# dualwbo.net
KiCad netlist of a schematic drawn in EAGLE
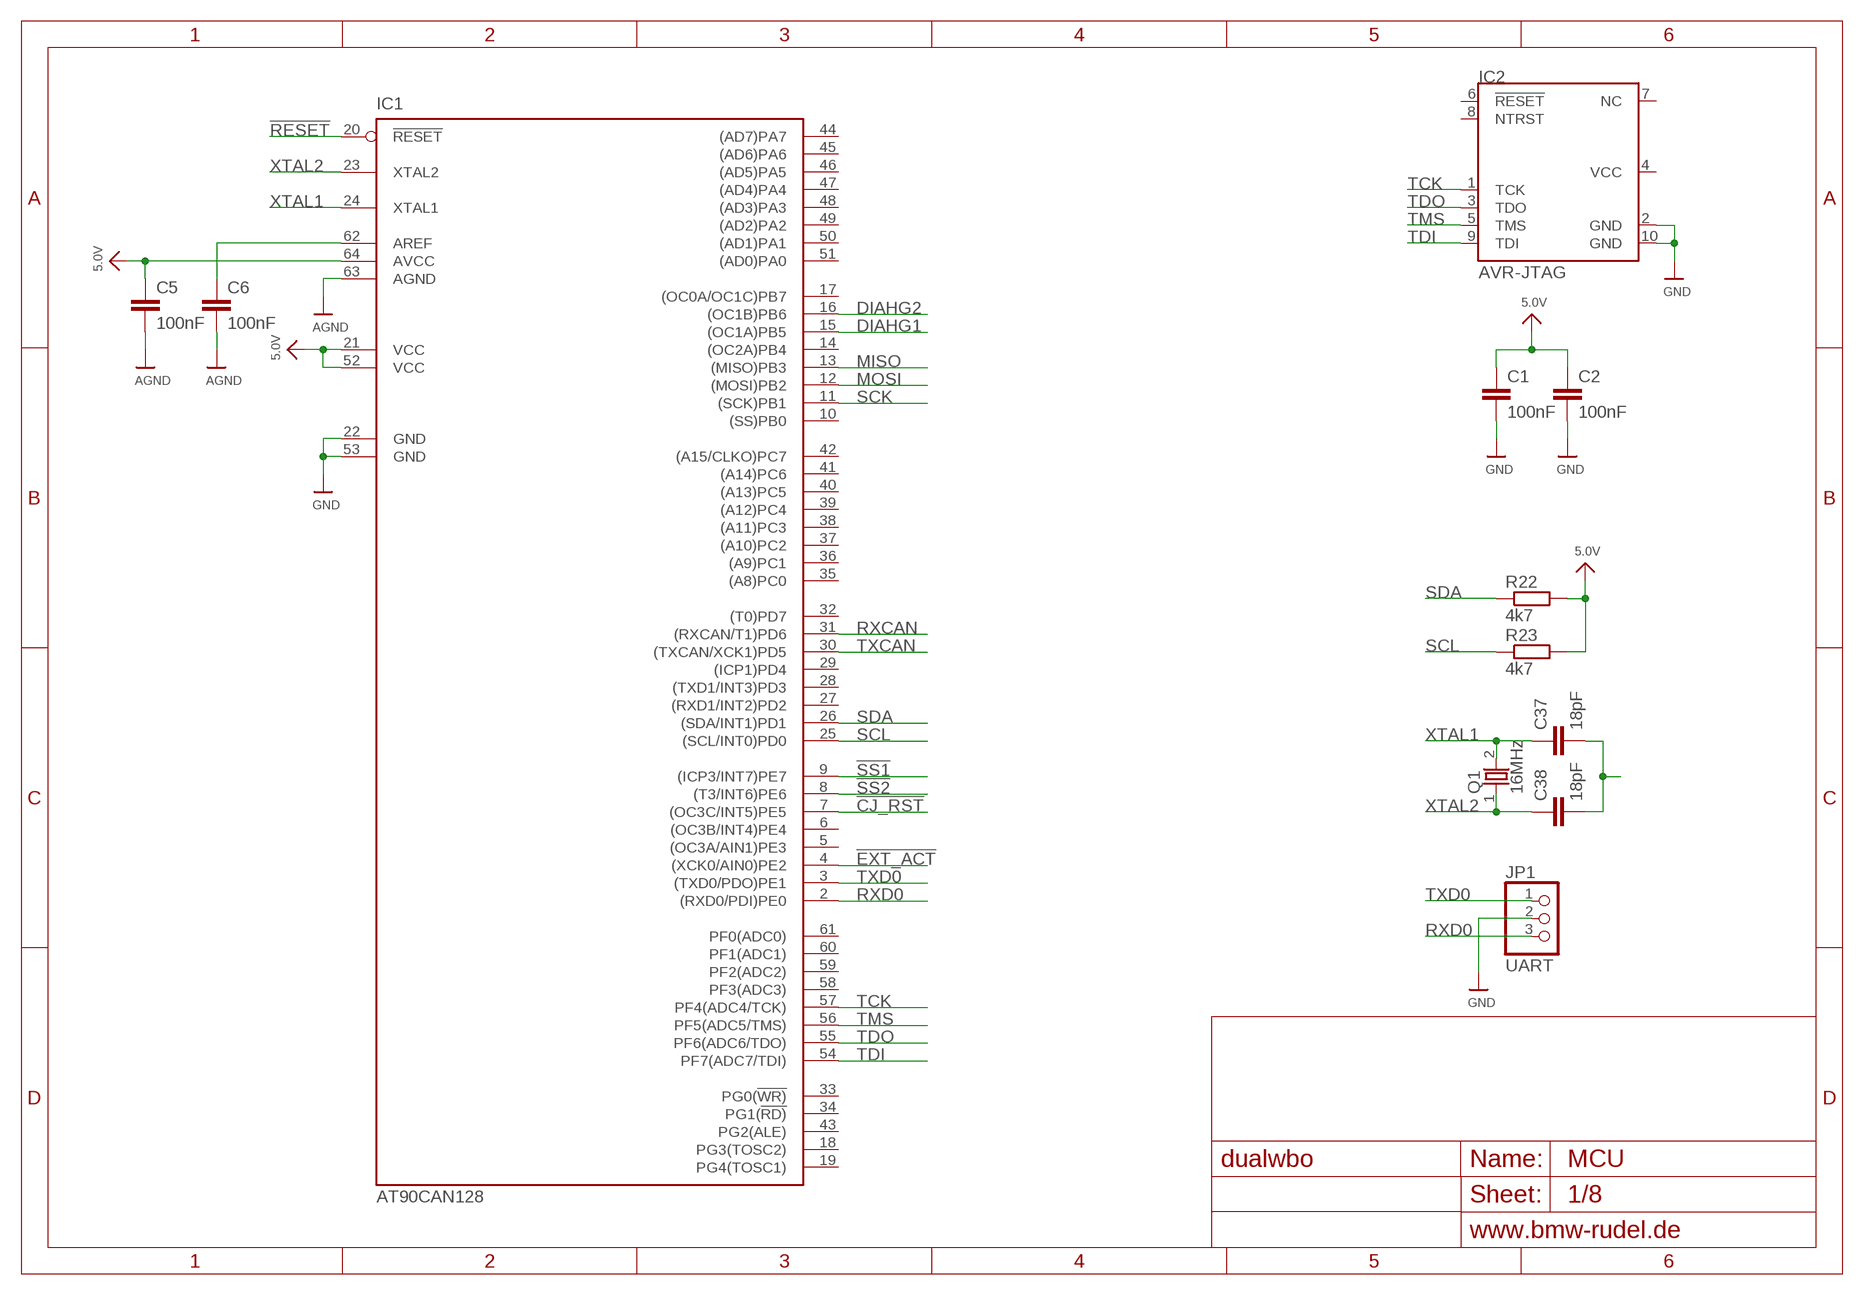
[diagram p0: schematic, sheet 1]
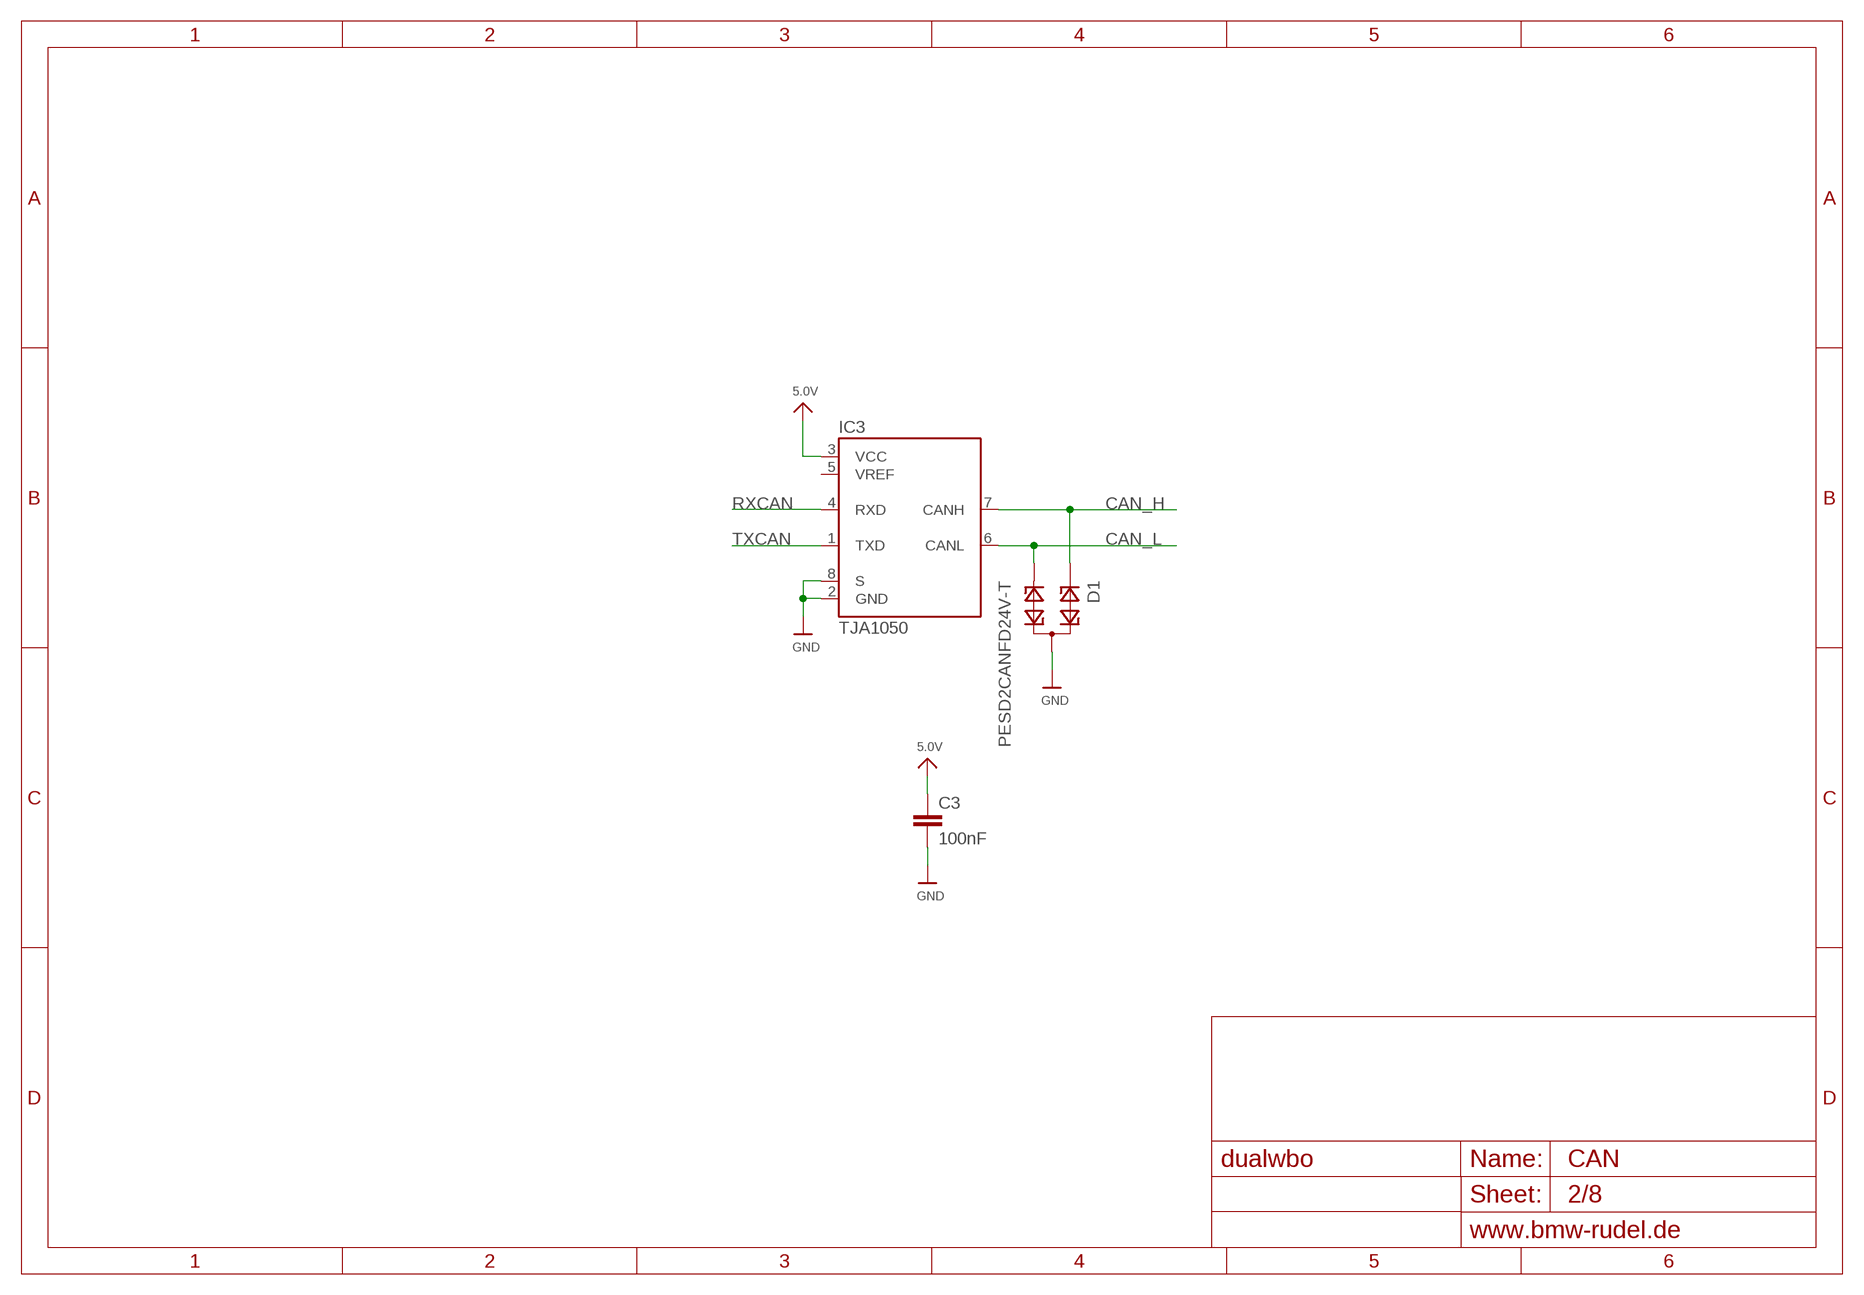
[diagram p1: schematic, sheet 2]
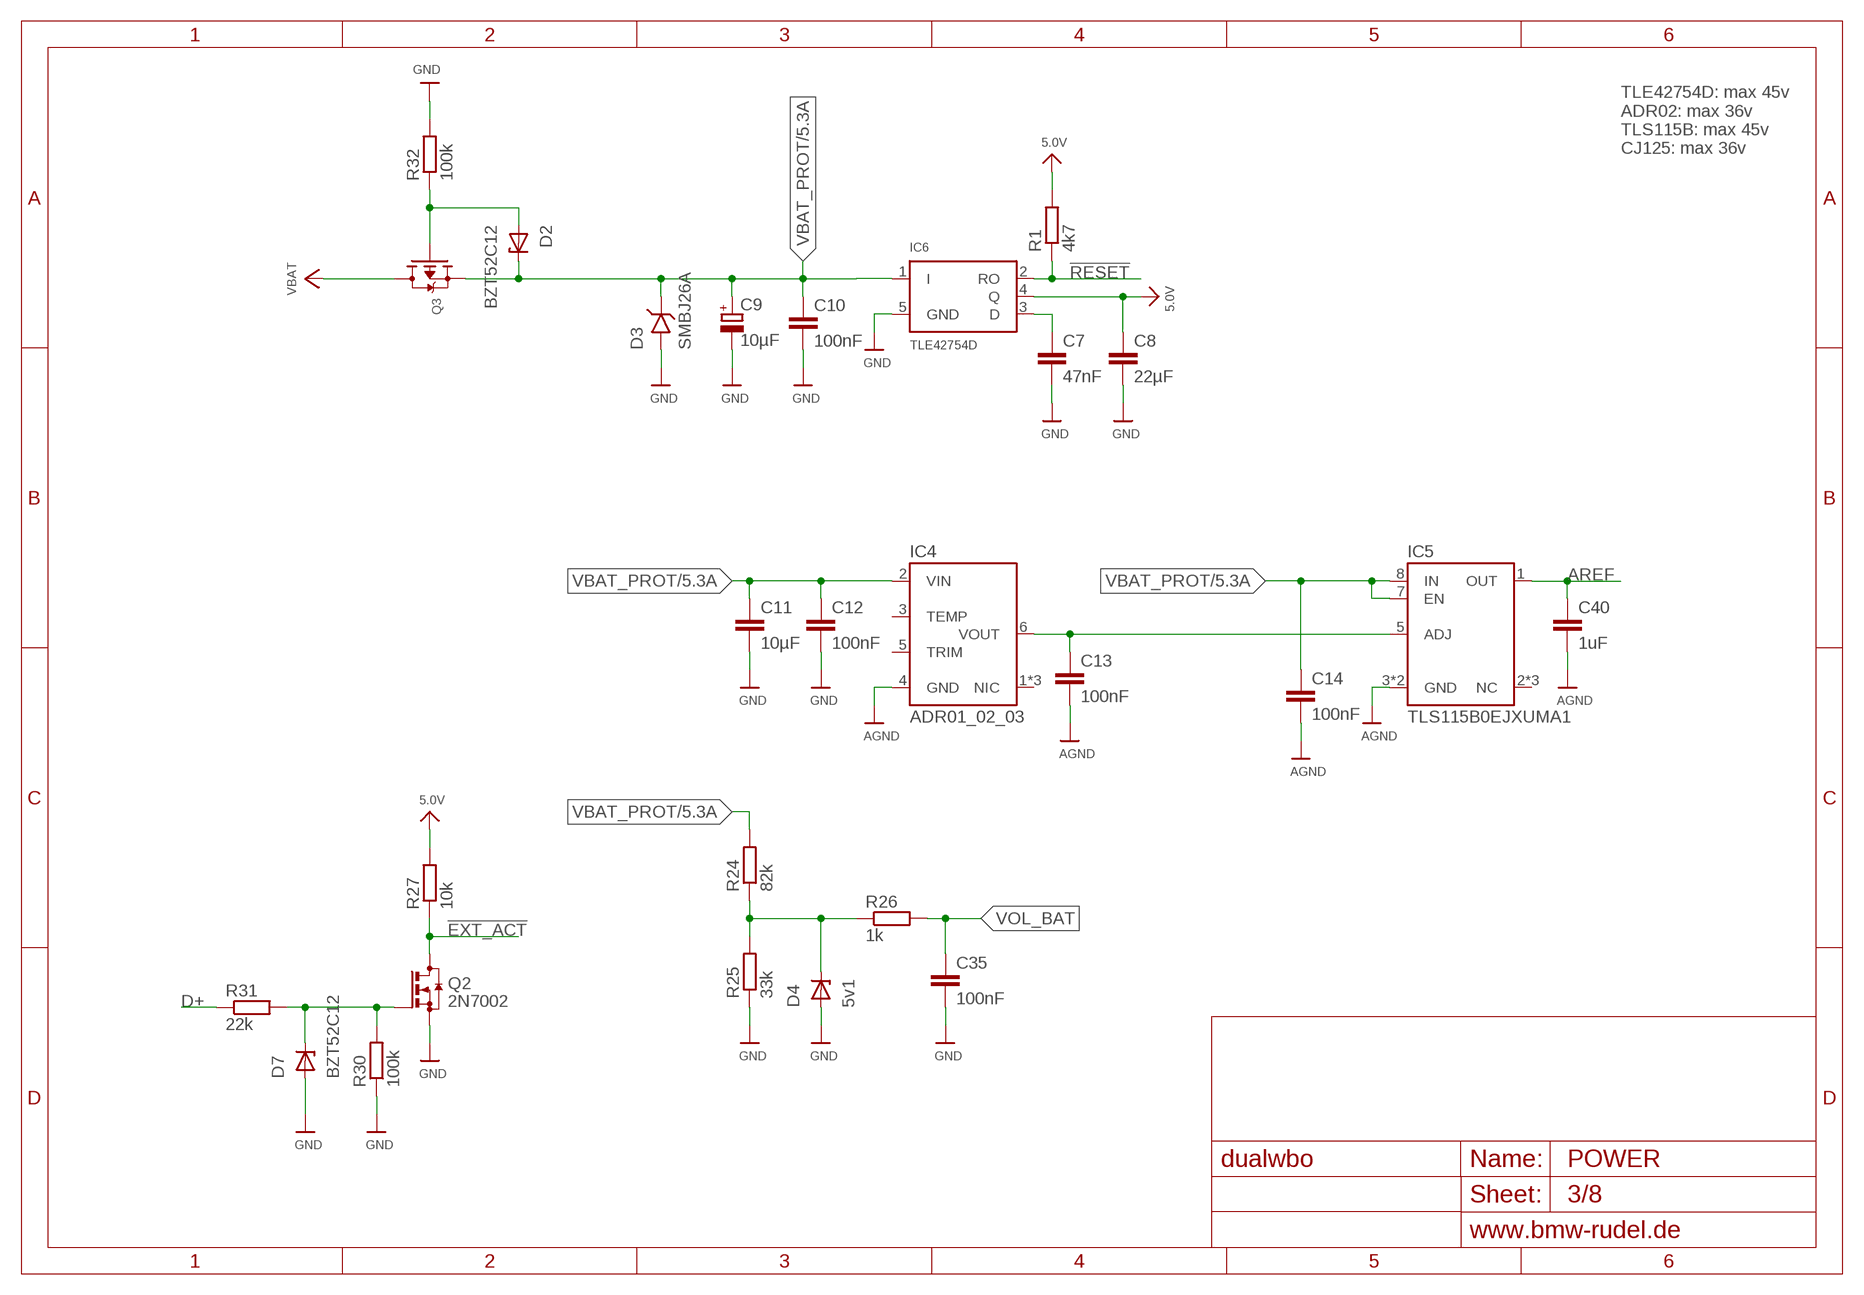
[diagram p2: schematic, sheet 3]
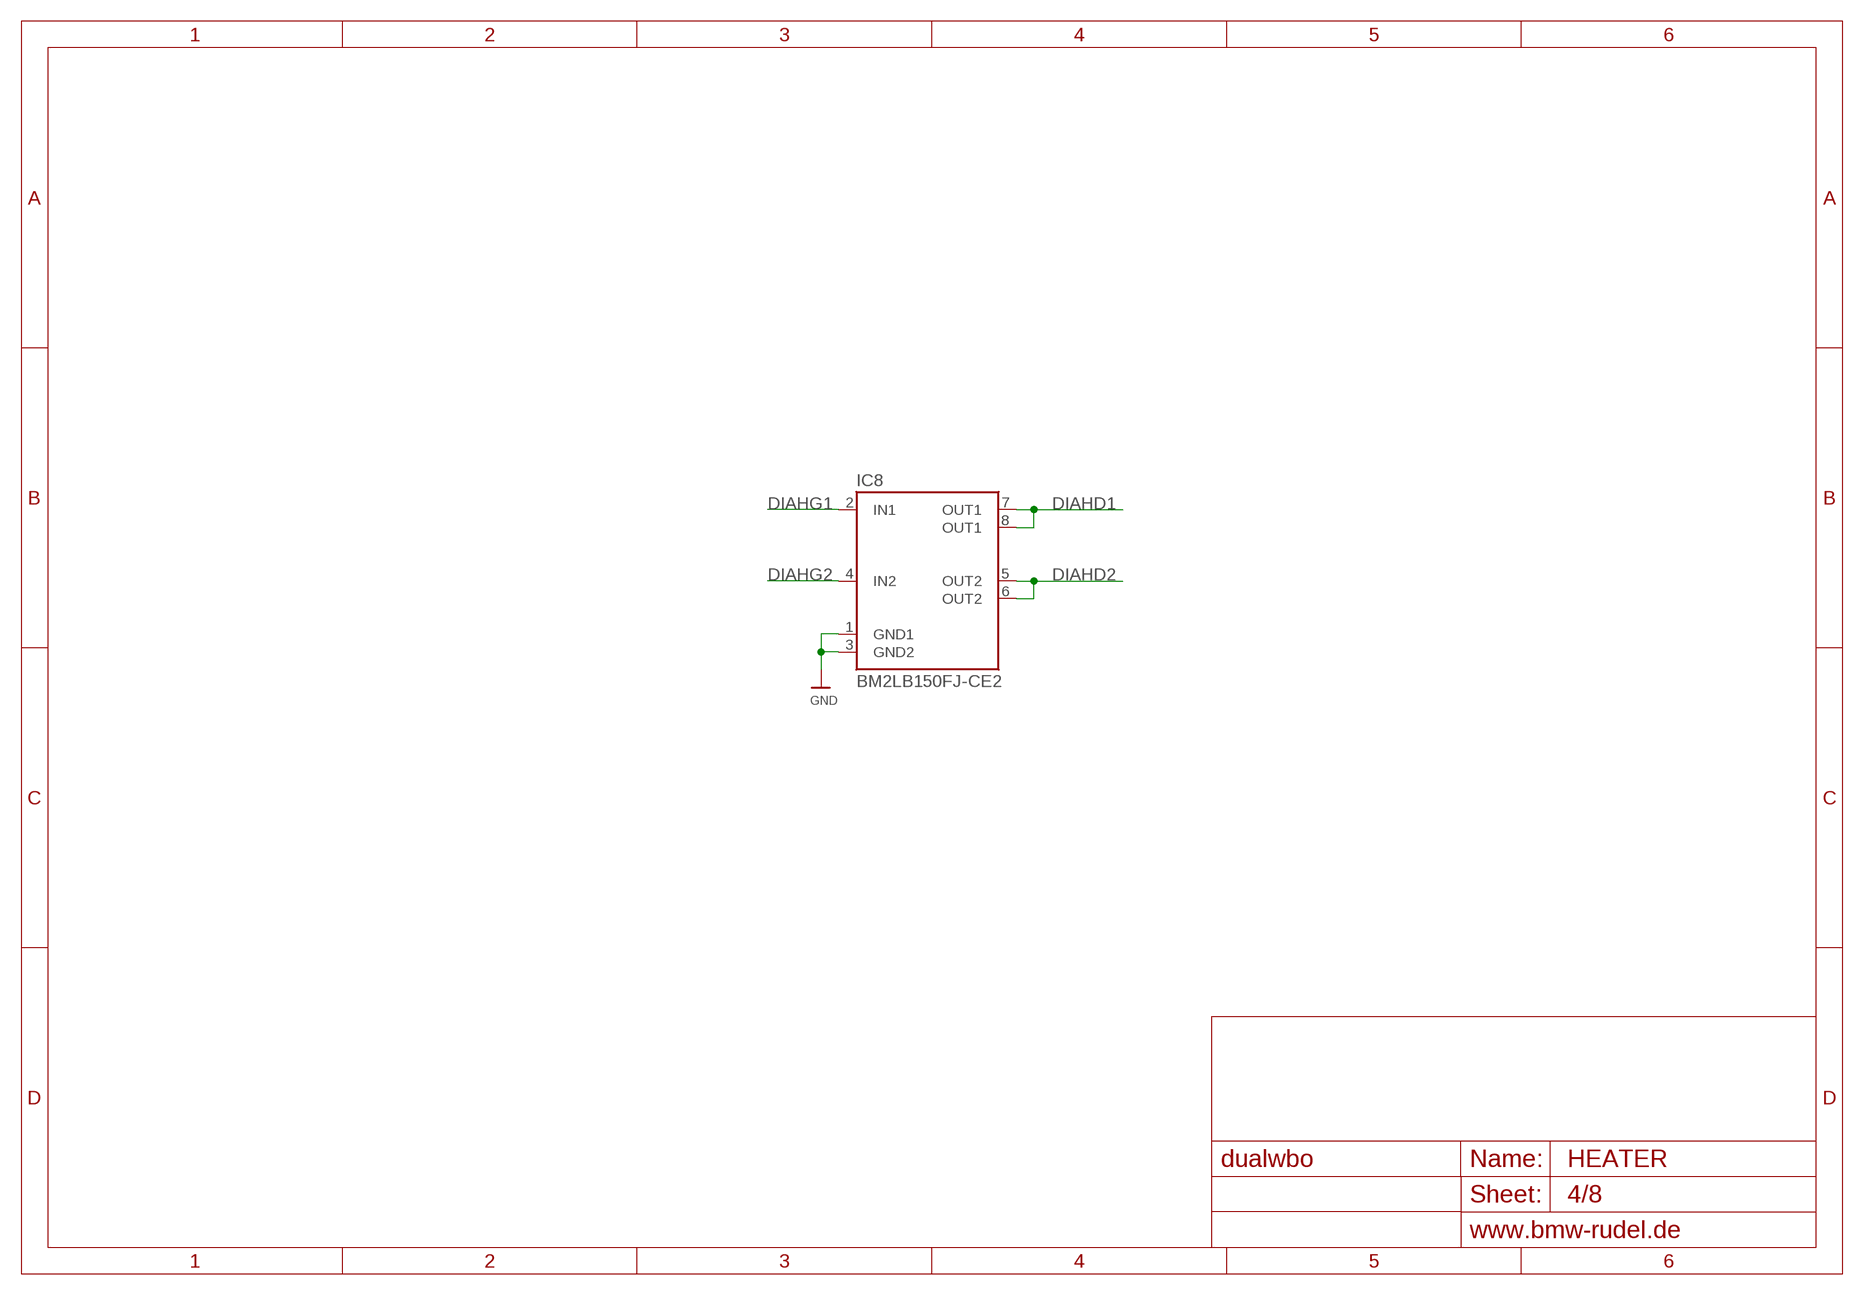
[diagram p3: schematic, sheet 4]
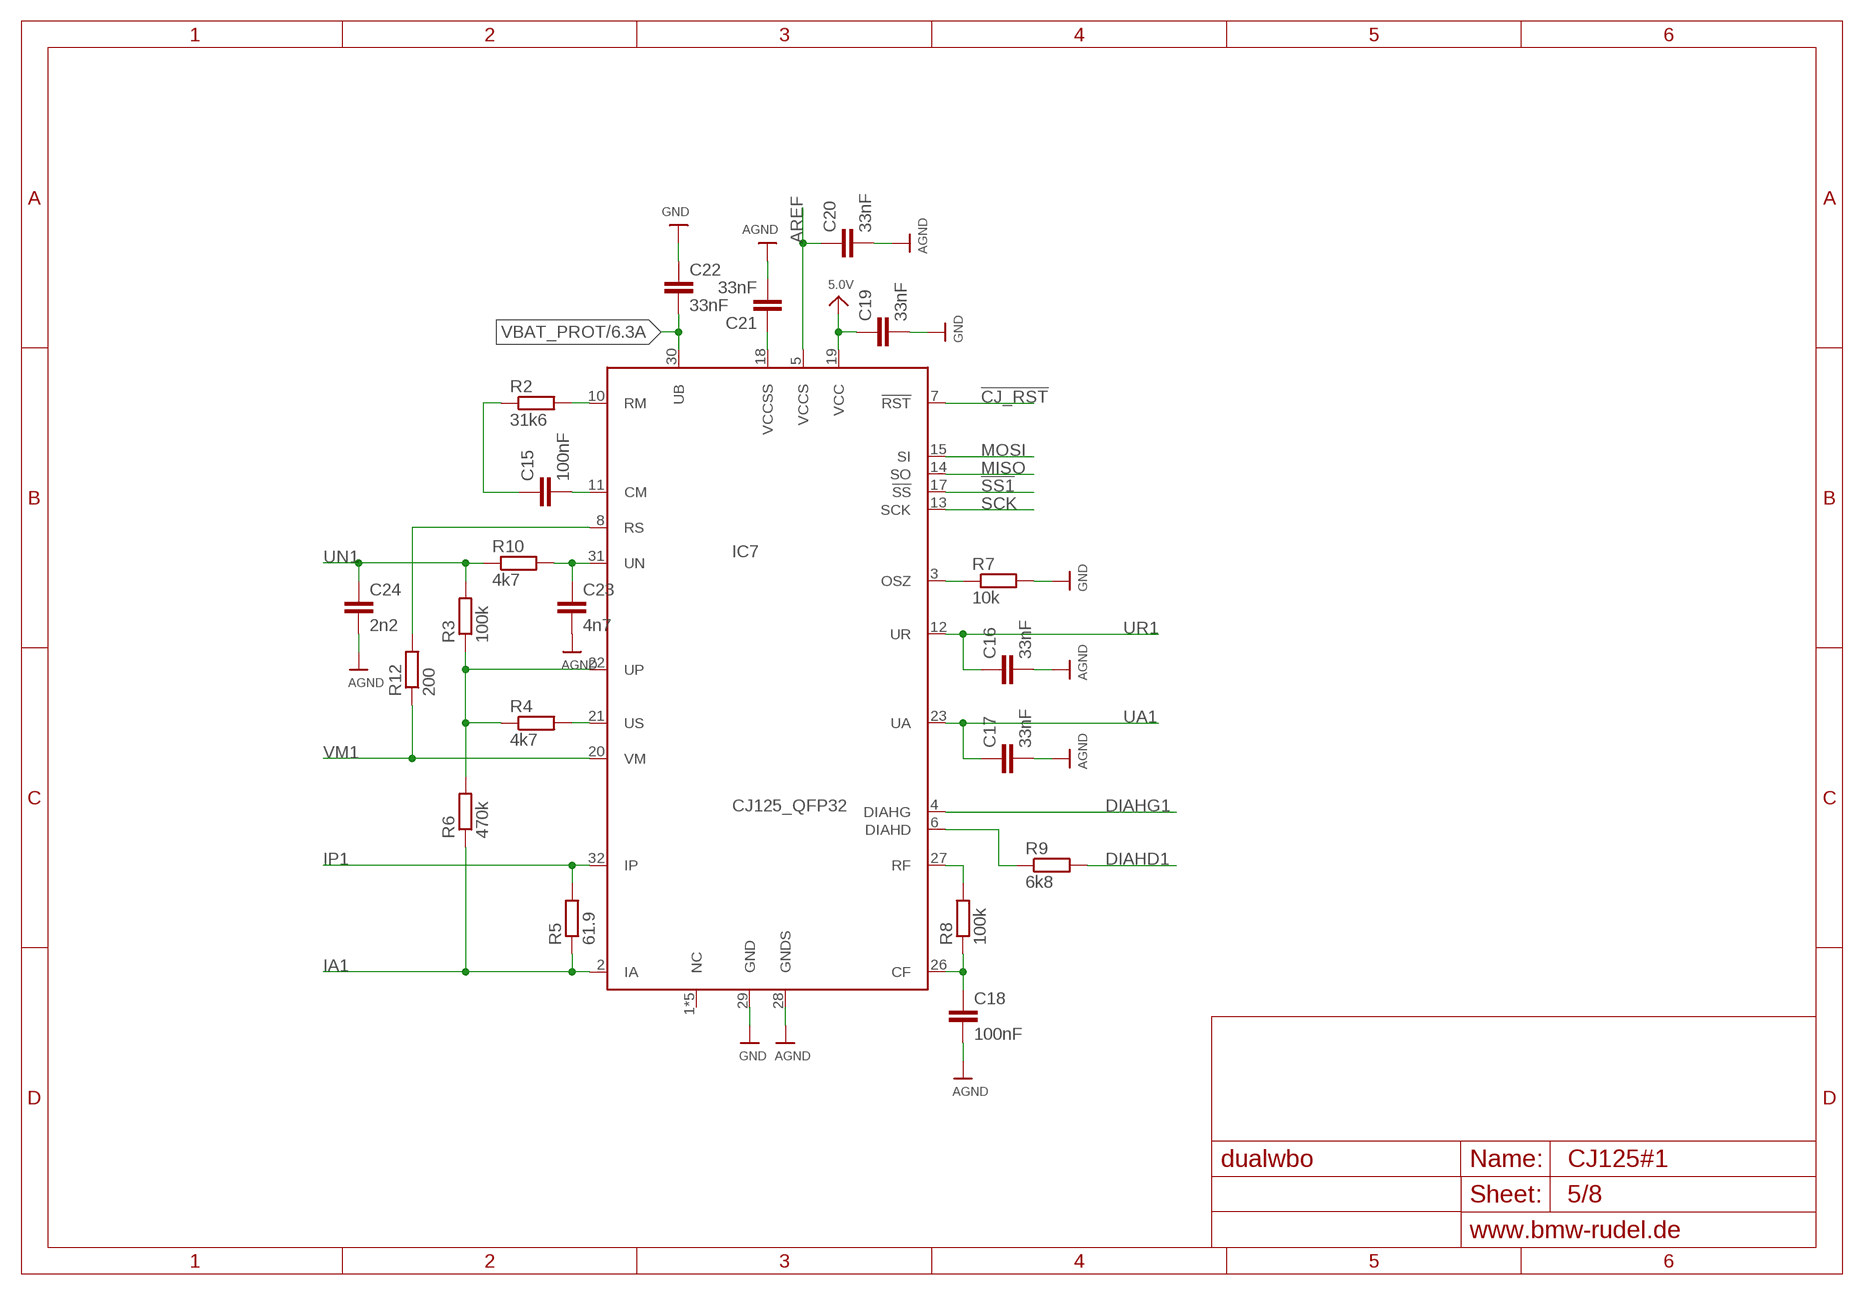
[diagram p4: schematic, sheet 5]
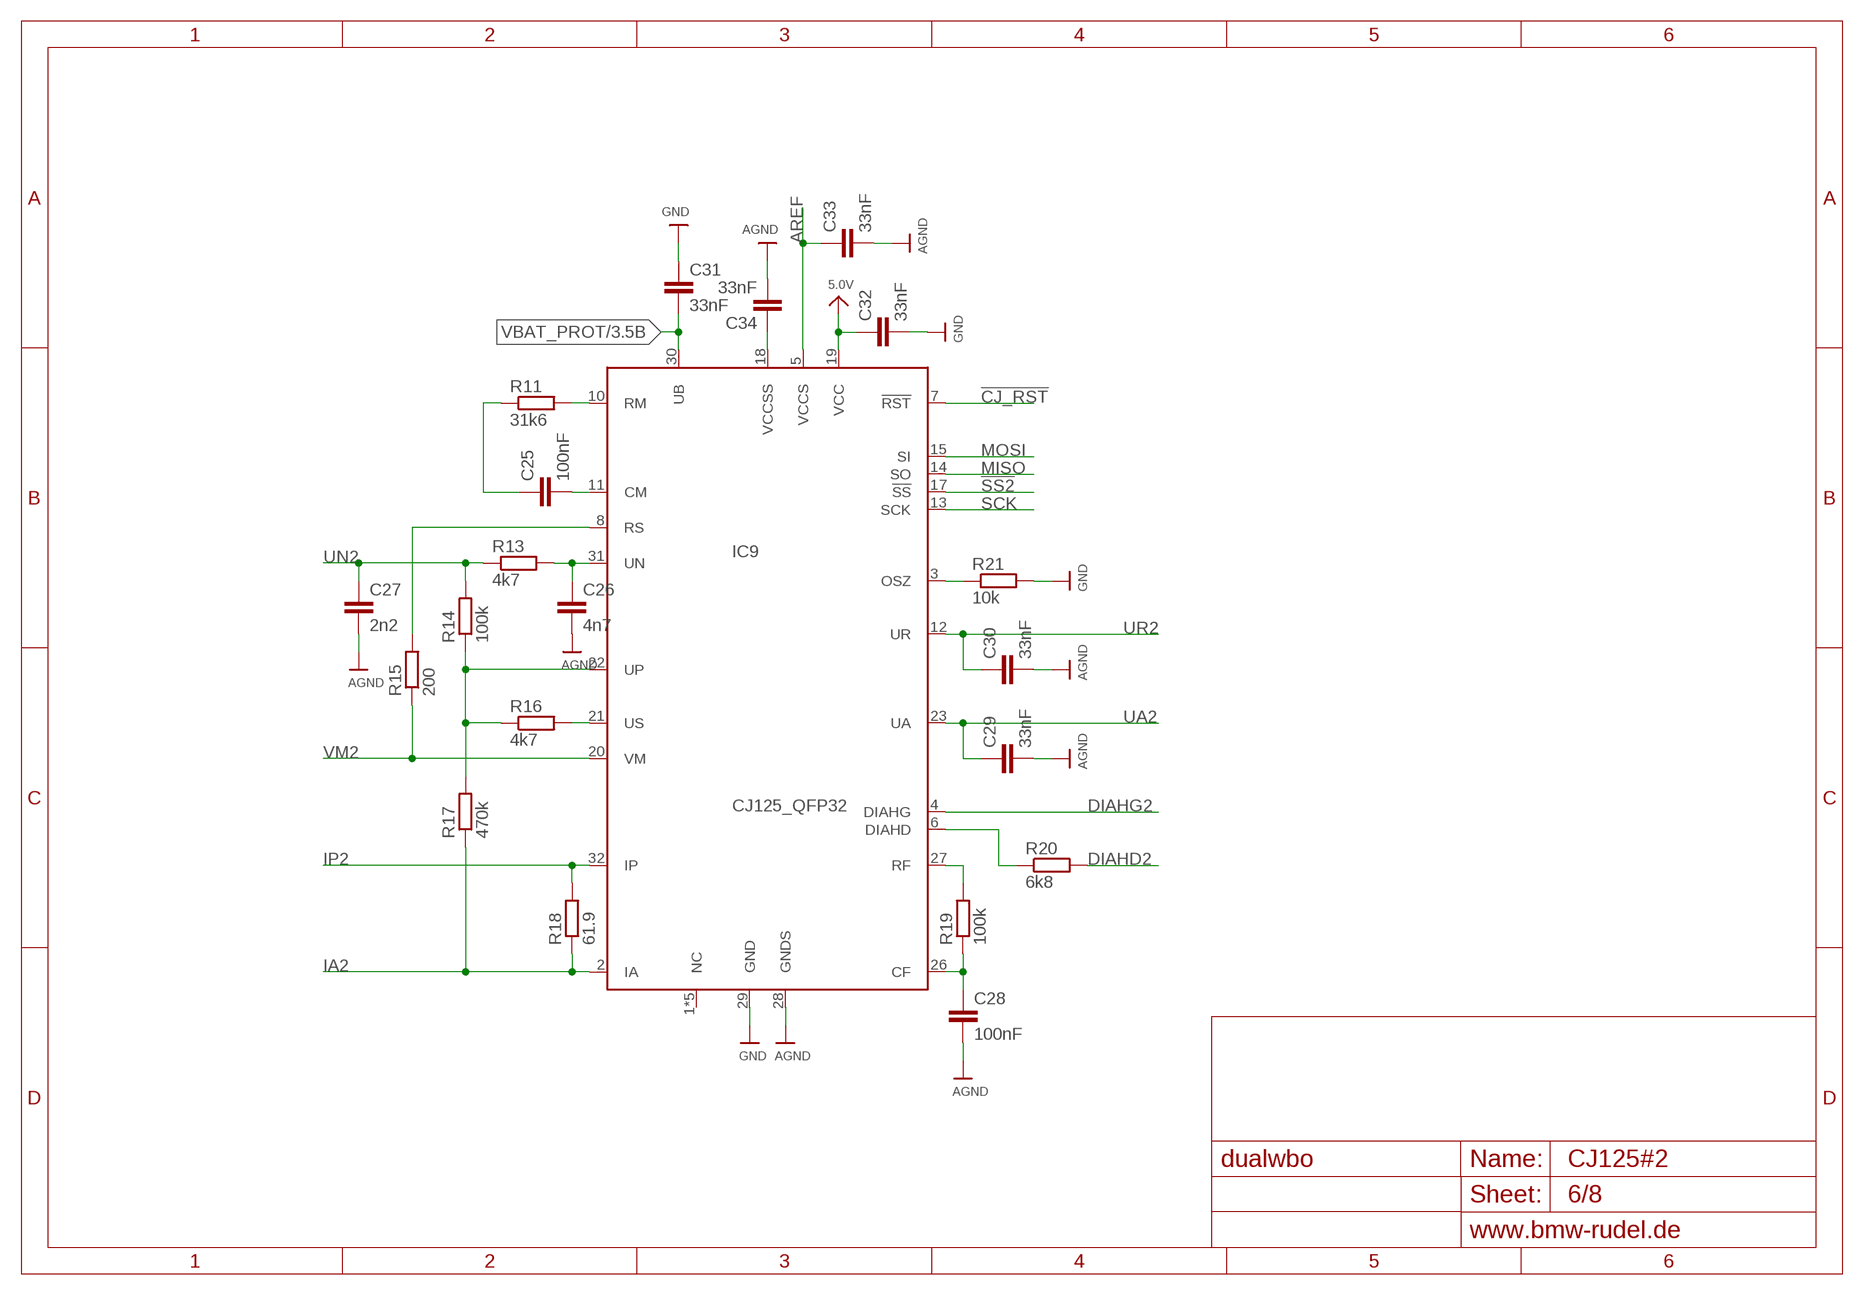
[diagram p5: schematic, sheet 6]
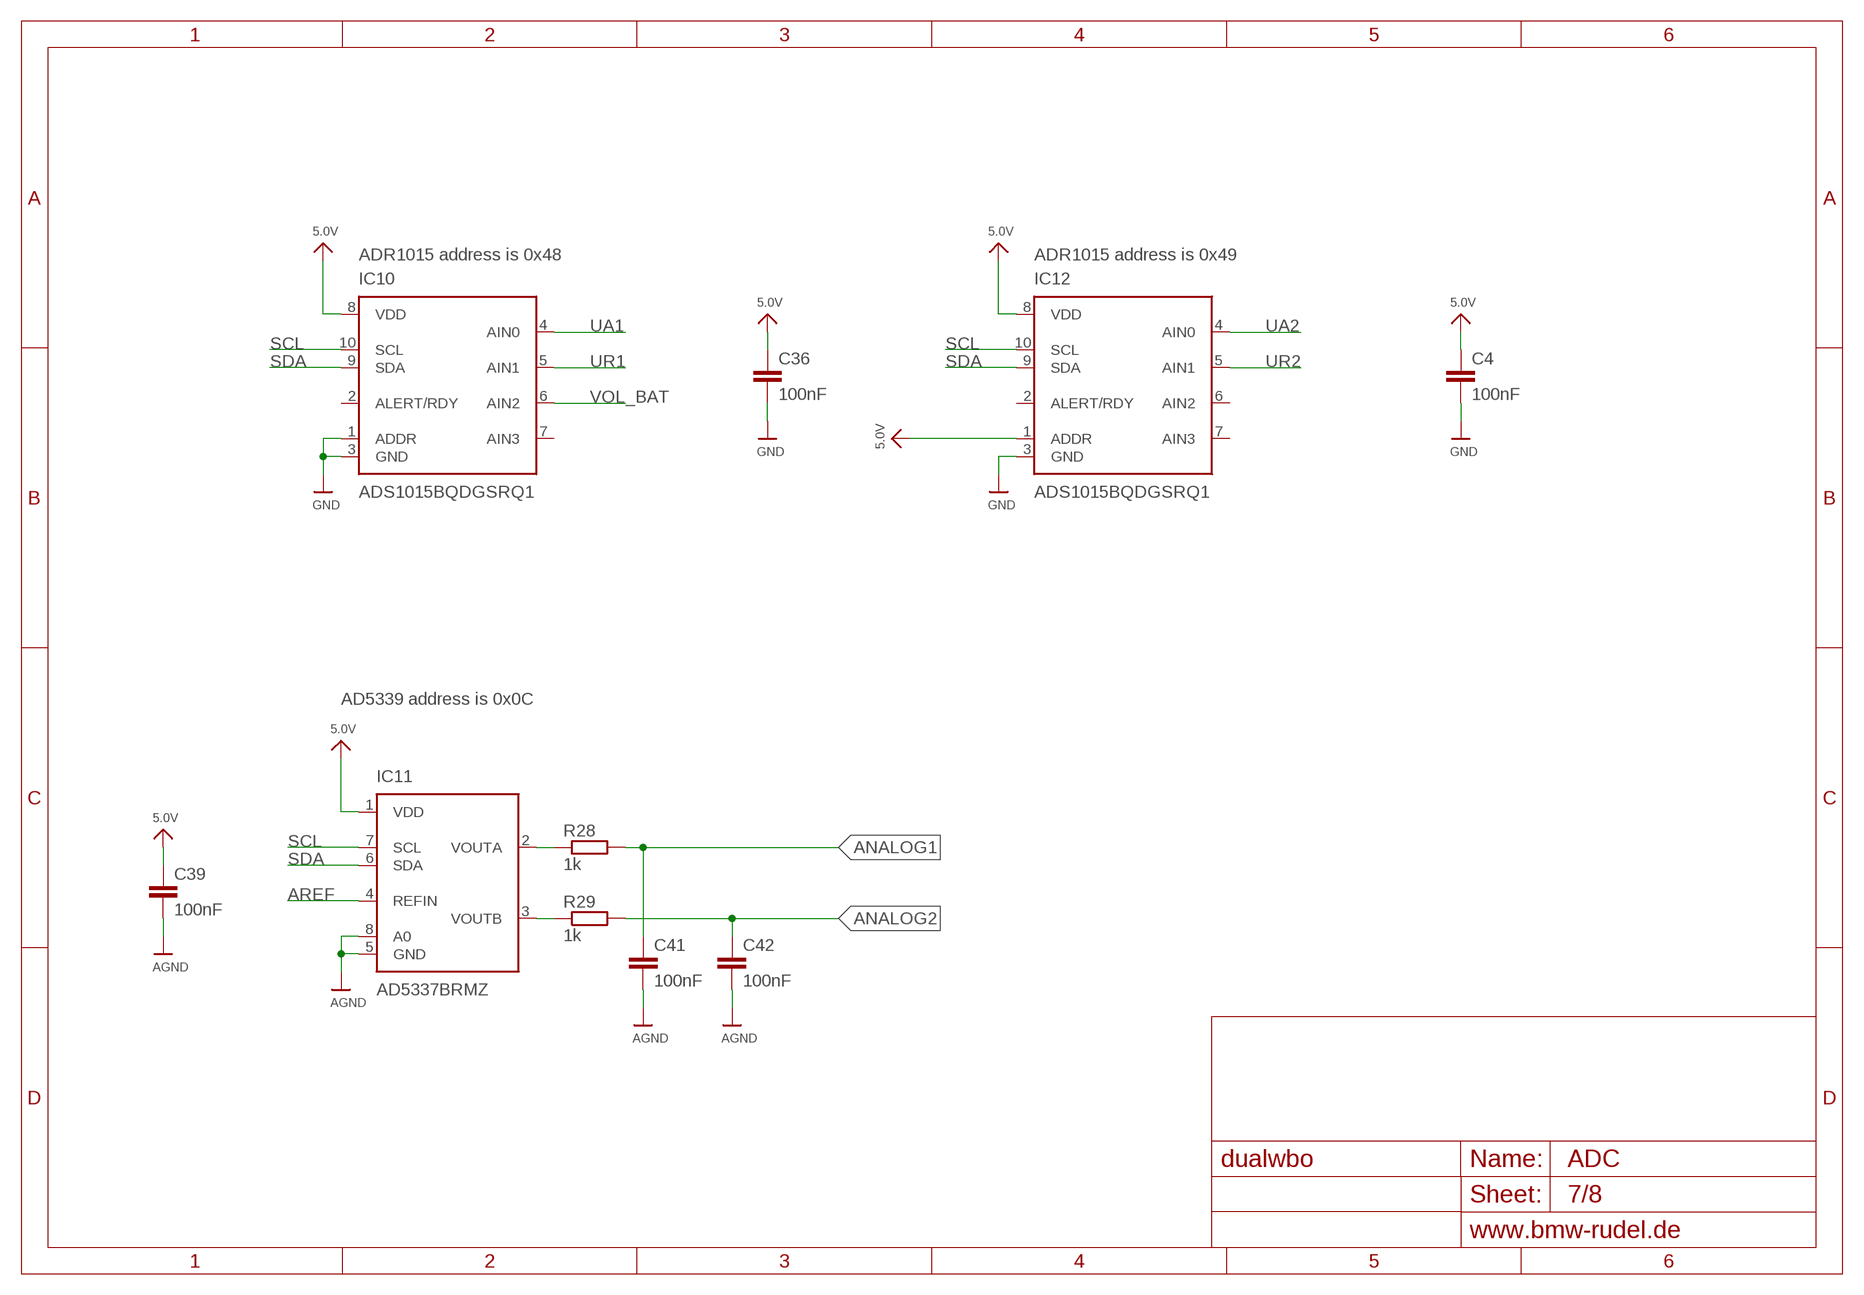
[diagram p6: schematic, sheet 7]
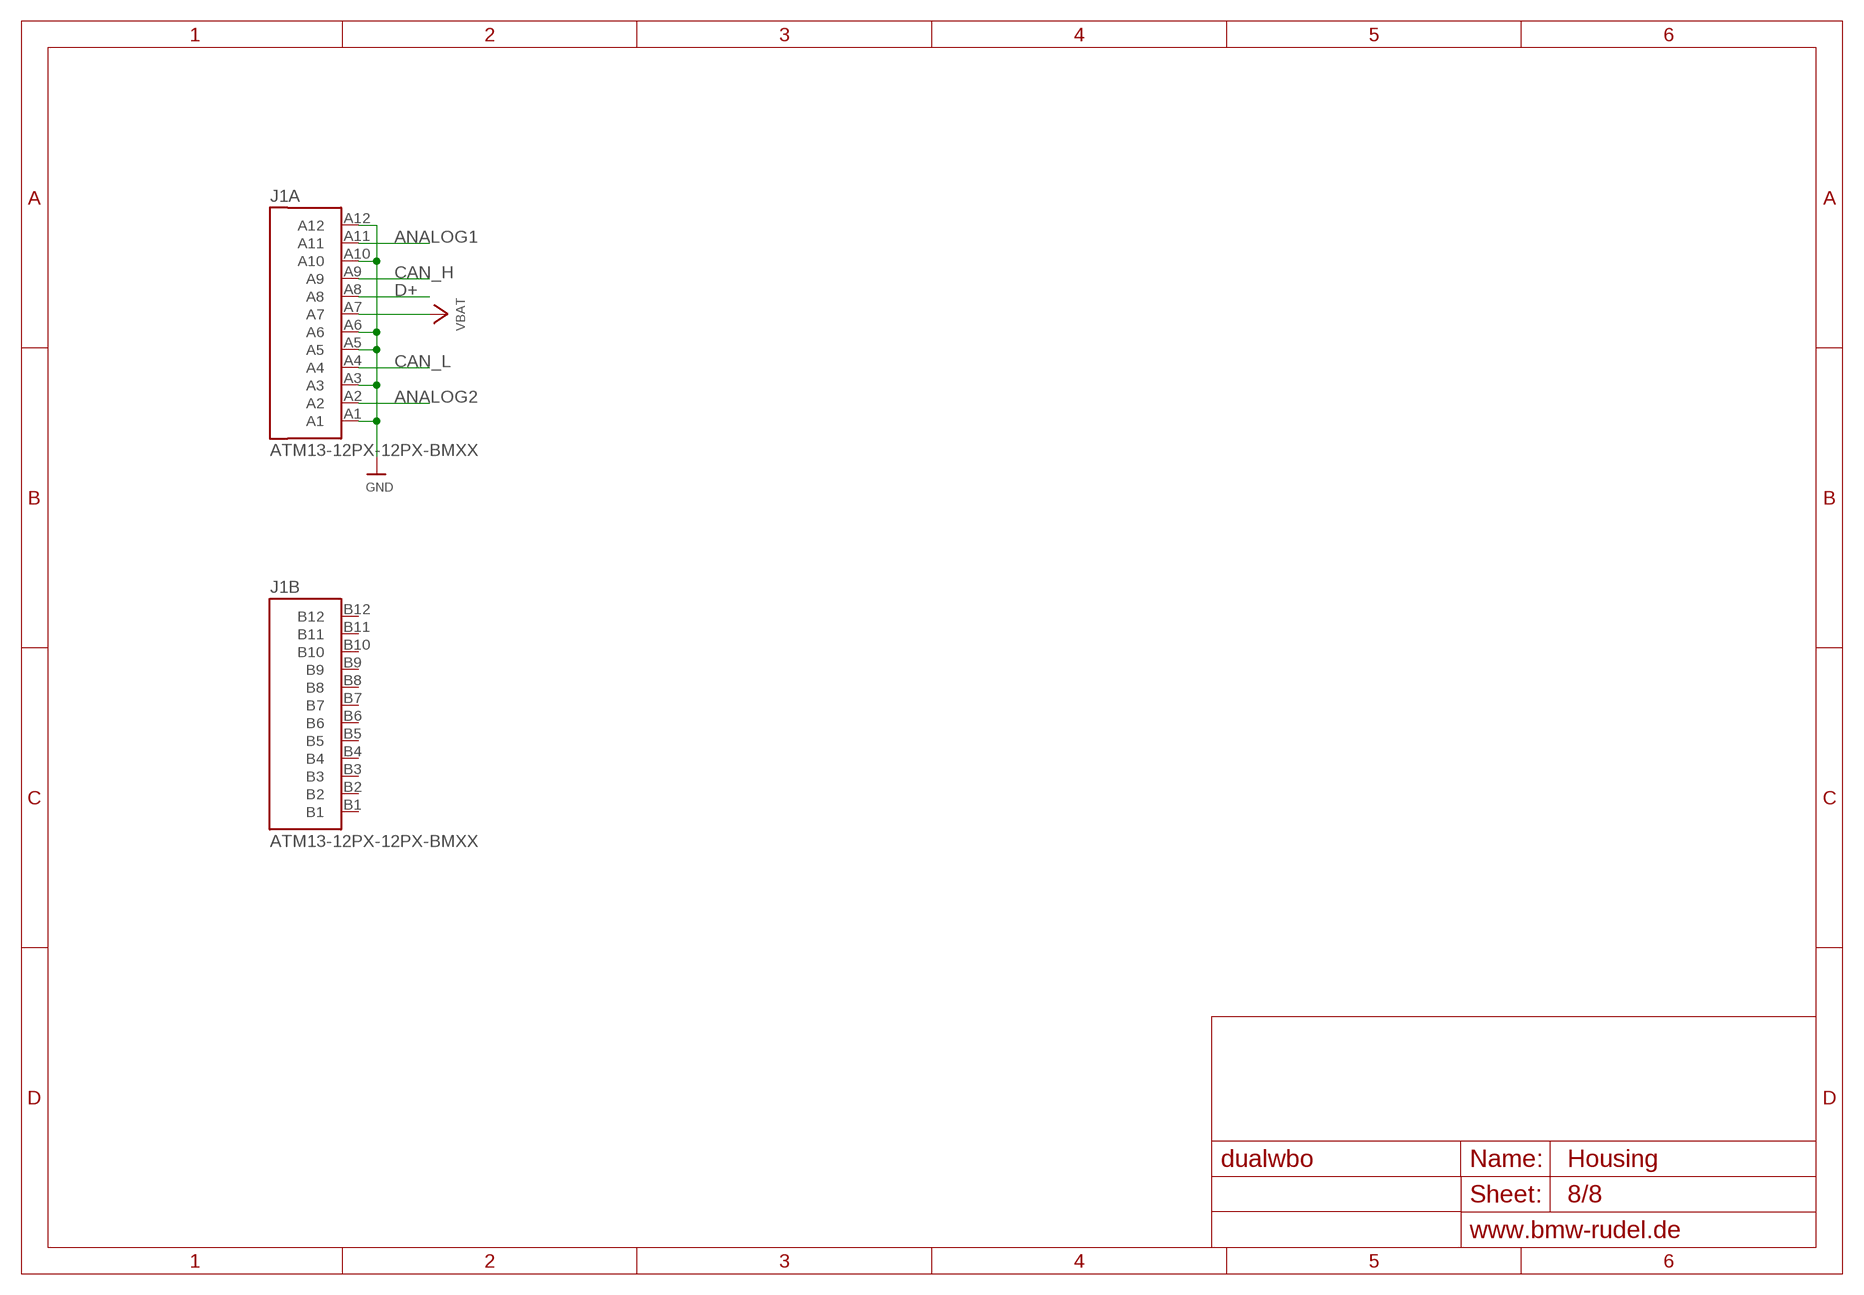
[diagram p7: schematic, sheet 8]

(export (version "E")
  (design (tool "Eeschema 10.0.6"))
  (components
    (comp (ref "C1")
      (value "100nF")
      (footprint "eagle-import:C0805")
      (libsource (lib "eagle-import") (part "C-EUC0805"))
    )
    (comp (ref "C2")
      (value "100nF")
      (footprint "eagle-import:C0805")
      (libsource (lib "eagle-import") (part "C-EUC0805"))
    )
    (comp (ref "C5")
      (value "100nF")
      (footprint "eagle-import:C0805")
      (libsource (lib "eagle-import") (part "C-EUC0805"))
    )
    (comp (ref "C6")
      (value "100nF")
      (footprint "eagle-import:C0805")
      (libsource (lib "eagle-import") (part "C-EUC0805"))
    )
    (comp (ref "C37")
      (value "18pF")
      (footprint "eagle-import:C0805")
      (libsource (lib "eagle-import") (part "C-EUC0805"))
    )
    (comp (ref "C38")
      (value "18pF")
      (footprint "eagle-import:C0805")
      (libsource (lib "eagle-import") (part "C-EUC0805"))
    )
    (comp (ref "IC1")
      (value "AT90CAN128")
      (footprint "eagle-import:TQFP64")
      (libsource (lib "eagle-import") (part "AT90CAN128"))
    )
    (comp (ref "IC2")
      (value "AVR-JTAG")
      (footprint "eagle-import:2X05_1.27MM_SMT")
      (libsource (lib "eagle-import") (part "AVR-JTAG"))
    )
    (comp (ref "JP1")
      (value "UART")
      (footprint "eagle-import:1X03")
      (libsource (lib "eagle-import") (part "PINHD-1X3"))
    )
    (comp (ref "Q1")
      (value "16MHz")
      (footprint "eagle-import:ABM7")
      (libsource (lib "eagle-import") (part "ABM7"))
    )
    (comp (ref "R22")
      (value "4k7")
      (footprint "eagle-import:R0805")
      (libsource (lib "eagle-import") (part "R-EU_R0805"))
    )
    (comp (ref "R23")
      (value "4k7")
      (footprint "eagle-import:R0805")
      (libsource (lib "eagle-import") (part "R-EU_R0805"))
    )
    (comp (ref "C15")
      (value "100nF")
      (footprint "eagle-import:C0805")
      (libsource (lib "eagle-import") (part "C-EUC0805"))
    )
    (comp (ref "C16")
      (value "33nF")
      (footprint "eagle-import:C0805")
      (libsource (lib "eagle-import") (part "C-EUC0805"))
    )
    (comp (ref "C17")
      (value "33nF")
      (footprint "eagle-import:C0805")
      (libsource (lib "eagle-import") (part "C-EUC0805"))
    )
    (comp (ref "C18")
      (value "100nF")
      (footprint "eagle-import:C0805")
      (libsource (lib "eagle-import") (part "C-EUC0805"))
    )
    (comp (ref "C19")
      (value "33nF")
      (footprint "eagle-import:C0805")
      (libsource (lib "eagle-import") (part "C-EUC0805"))
    )
    (comp (ref "C20")
      (value "33nF")
      (footprint "eagle-import:C0805")
      (libsource (lib "eagle-import") (part "C-EUC0805"))
    )
    (comp (ref "C21")
      (value "33nF")
      (footprint "eagle-import:C0805")
      (libsource (lib "eagle-import") (part "C-EUC0805"))
    )
    (comp (ref "C22")
      (value "33nF")
      (footprint "eagle-import:C0805")
      (libsource (lib "eagle-import") (part "C-EUC0805"))
    )
    (comp (ref "C23")
      (value "4n7")
      (footprint "eagle-import:C0805")
      (libsource (lib "eagle-import") (part "C-EUC0805"))
    )
    (comp (ref "C24")
      (value "2n2")
      (footprint "eagle-import:C0805")
      (libsource (lib "eagle-import") (part "C-EUC0805"))
    )
    (comp (ref "IC7")
      (value "CJ125_QFP32")
      (footprint "eagle-import:TQFP32-08")
      (libsource (lib "eagle-import") (part "CJ125_QFP32"))
    )
    (comp (ref "R2")
      (value "31k6")
      (footprint "eagle-import:R0805")
      (libsource (lib "eagle-import") (part "R-EU_R0805"))
    )
    (comp (ref "R3")
      (value "100k")
      (footprint "eagle-import:R0805")
      (libsource (lib "eagle-import") (part "R-EU_R0805"))
    )
    (comp (ref "R4")
      (value "4k7")
      (footprint "eagle-import:R0805")
      (libsource (lib "eagle-import") (part "R-EU_R0805"))
    )
    (comp (ref "R5")
      (value "61.9")
      (footprint "eagle-import:R0805")
      (libsource (lib "eagle-import") (part "R-EU_R0805"))
    )
    (comp (ref "R6")
      (value "470k")
      (footprint "eagle-import:R0805")
      (libsource (lib "eagle-import") (part "R-EU_R0805"))
    )
    (comp (ref "R7")
      (value "10k")
      (footprint "eagle-import:R0805")
      (libsource (lib "eagle-import") (part "R-EU_R0805"))
    )
    (comp (ref "R8")
      (value "100k")
      (footprint "eagle-import:R0805")
      (libsource (lib "eagle-import") (part "R-EU_R0805"))
    )
    (comp (ref "R9")
      (value "6k8")
      (footprint "eagle-import:R0805")
      (libsource (lib "eagle-import") (part "R-EU_R0805"))
    )
    (comp (ref "R10")
      (value "4k7")
      (footprint "eagle-import:R0805")
      (libsource (lib "eagle-import") (part "R-EU_R0805"))
    )
    (comp (ref "R12")
      (value "200")
      (footprint "eagle-import:R0805")
      (libsource (lib "eagle-import") (part "R-EU_R0805"))
    )
    (comp (ref "J1")
      (value "ATM13-12PX-12PX-BMXX")
      (footprint "eagle-import:ATM13-12PX-12PX-BMXX")
      (libsource (lib "eagle-import") (part "ATM13-12PX-12PX-BMXX"))
    )
    (comp (ref "C4")
      (value "100nF")
      (footprint "eagle-import:C0805")
      (libsource (lib "eagle-import") (part "C-EUC0805"))
    )
    (comp (ref "C36")
      (value "100nF")
      (footprint "eagle-import:C0805")
      (libsource (lib "eagle-import") (part "C-EUC0805"))
    )
    (comp (ref "C39")
      (value "100nF")
      (footprint "eagle-import:C0805")
      (libsource (lib "eagle-import") (part "C-EUC0805"))
    )
    (comp (ref "C41")
      (value "100nF")
      (footprint "eagle-import:C0805")
      (libsource (lib "eagle-import") (part "C-EUC0805"))
    )
    (comp (ref "C42")
      (value "100nF")
      (footprint "eagle-import:C0805")
      (libsource (lib "eagle-import") (part "C-EUC0805"))
    )
    (comp (ref "IC10")
      (value "ADS1015BQDGSRQ1")
      (footprint "eagle-import:SOP50P490X110-10N")
      (fields (field (name "MOUSER_PART_NUMBER") "595-ADS1015BQDGSRQ1"))
      (libsource (lib "eagle-import") (part "ADS1015BQDGSRQ1"))
    )
    (comp (ref "IC11")
      (value "AD5337BRMZ")
      (footprint "eagle-import:SOP65P490X110-8N")
      (fields (field (name "MOUSER_PART_NUMBER") "584-AD5337BRMZ"))
      (libsource (lib "eagle-import") (part "AD5337BRMZ"))
    )
    (comp (ref "IC12")
      (value "ADS1015BQDGSRQ1")
      (footprint "eagle-import:SOP50P490X110-10N")
      (fields (field (name "MOUSER_PART_NUMBER") "595-ADS1015BQDGSRQ1"))
      (libsource (lib "eagle-import") (part "ADS1015BQDGSRQ1"))
    )
    (comp (ref "R28")
      (value "1k")
      (footprint "eagle-import:R0805")
      (libsource (lib "eagle-import") (part "R-EU_R0805"))
    )
    (comp (ref "R29")
      (value "1k")
      (footprint "eagle-import:R0805")
      (libsource (lib "eagle-import") (part "R-EU_R0805"))
    )
    (comp (ref "C3")
      (value "100nF")
      (footprint "eagle-import:C0805")
      (libsource (lib "eagle-import") (part "C-EUC0805"))
    )
    (comp (ref "D1")
      (value "PESD2CANFD24V-T")
      (footprint "eagle-import:SOT23")
      (libsource (lib "eagle-import") (part "PESD2CANFD24V-T"))
    )
    (comp (ref "IC3")
      (value "TJA1050")
      (footprint "eagle-import:SO8")
      (libsource (lib "eagle-import") (part "TJA1050"))
    )
    (comp (ref "C25")
      (value "100nF")
      (footprint "eagle-import:C0805")
      (libsource (lib "eagle-import") (part "C-EUC0805"))
    )
    (comp (ref "C26")
      (value "4n7")
      (footprint "eagle-import:C0805")
      (libsource (lib "eagle-import") (part "C-EUC0805"))
    )
    (comp (ref "C27")
      (value "2n2")
      (footprint "eagle-import:C0805")
      (libsource (lib "eagle-import") (part "C-EUC0805"))
    )
    (comp (ref "C28")
      (value "100nF")
      (footprint "eagle-import:C0805")
      (libsource (lib "eagle-import") (part "C-EUC0805"))
    )
    (comp (ref "C29")
      (value "33nF")
      (footprint "eagle-import:C0805")
      (libsource (lib "eagle-import") (part "C-EUC0805"))
    )
    (comp (ref "C30")
      (value "33nF")
      (footprint "eagle-import:C0805")
      (libsource (lib "eagle-import") (part "C-EUC0805"))
    )
    (comp (ref "C31")
      (value "33nF")
      (footprint "eagle-import:C0805")
      (libsource (lib "eagle-import") (part "C-EUC0805"))
    )
    (comp (ref "C32")
      (value "33nF")
      (footprint "eagle-import:C0805")
      (libsource (lib "eagle-import") (part "C-EUC0805"))
    )
    (comp (ref "C33")
      (value "33nF")
      (footprint "eagle-import:C0805")
      (libsource (lib "eagle-import") (part "C-EUC0805"))
    )
    (comp (ref "C34")
      (value "33nF")
      (footprint "eagle-import:C0805")
      (libsource (lib "eagle-import") (part "C-EUC0805"))
    )
    (comp (ref "IC9")
      (value "CJ125_QFP32")
      (footprint "eagle-import:TQFP32-08")
      (libsource (lib "eagle-import") (part "CJ125_QFP32"))
    )
    (comp (ref "R11")
      (value "31k6")
      (footprint "eagle-import:R0805")
      (libsource (lib "eagle-import") (part "R-EU_R0805"))
    )
    (comp (ref "R13")
      (value "4k7")
      (footprint "eagle-import:R0805")
      (libsource (lib "eagle-import") (part "R-EU_R0805"))
    )
    (comp (ref "R14")
      (value "100k")
      (footprint "eagle-import:R0805")
      (libsource (lib "eagle-import") (part "R-EU_R0805"))
    )
    (comp (ref "R15")
      (value "200")
      (footprint "eagle-import:R0805")
      (libsource (lib "eagle-import") (part "R-EU_R0805"))
    )
    (comp (ref "R16")
      (value "4k7")
      (footprint "eagle-import:R0805")
      (libsource (lib "eagle-import") (part "R-EU_R0805"))
    )
    (comp (ref "R17")
      (value "470k")
      (footprint "eagle-import:R0805")
      (libsource (lib "eagle-import") (part "R-EU_R0805"))
    )
    (comp (ref "R18")
      (value "61.9")
      (footprint "eagle-import:R0805")
      (libsource (lib "eagle-import") (part "R-EU_R0805"))
    )
    (comp (ref "R19")
      (value "100k")
      (footprint "eagle-import:R0805")
      (libsource (lib "eagle-import") (part "R-EU_R0805"))
    )
    (comp (ref "R20")
      (value "6k8")
      (footprint "eagle-import:R0805")
      (libsource (lib "eagle-import") (part "R-EU_R0805"))
    )
    (comp (ref "R21")
      (value "10k")
      (footprint "eagle-import:R0805")
      (libsource (lib "eagle-import") (part "R-EU_R0805"))
    )
    (comp (ref "C7")
      (value "47nF")
      (footprint "eagle-import:C0805")
      (libsource (lib "eagle-import") (part "C-EUC0805"))
    )
    (comp (ref "C8")
      (value "22µF")
      (footprint "eagle-import:C0805")
      (libsource (lib "eagle-import") (part "C-EUC0805"))
    )
    (comp (ref "C9")
      (value "10µF")
      (footprint "eagle-import:PANASONIC_D")
      (libsource (lib "eagle-import") (part "CPOL-EUD"))
    )
    (comp (ref "C10")
      (value "100nF")
      (footprint "eagle-import:C0805")
      (libsource (lib "eagle-import") (part "C-EUC0805"))
    )
    (comp (ref "C11")
      (value "10µF")
      (footprint "eagle-import:C0805")
      (libsource (lib "eagle-import") (part "C-EUC0805"))
    )
    (comp (ref "C12")
      (value "100nF")
      (footprint "eagle-import:C0805")
      (libsource (lib "eagle-import") (part "C-EUC0805"))
    )
    (comp (ref "C13")
      (value "100nF")
      (footprint "eagle-import:C0805")
      (libsource (lib "eagle-import") (part "C-EUC0805"))
    )
    (comp (ref "C14")
      (value "100nF")
      (footprint "eagle-import:C0805")
      (libsource (lib "eagle-import") (part "C-EUC0805"))
    )
    (comp (ref "C35")
      (value "100nF")
      (footprint "eagle-import:C0805")
      (libsource (lib "eagle-import") (part "C-EUC0805"))
    )
    (comp (ref "C40")
      (value "1uF")
      (footprint "eagle-import:C0805")
      (libsource (lib "eagle-import") (part "C-EUC0805"))
    )
    (comp (ref "D2")
      (value "BZT52C12")
      (footprint "eagle-import:SOD-123")
      (libsource (lib "eagle-import") (part "Z-DIODESOD123"))
    )
    (comp (ref "D3")
      (value "SMBJ26A")
      (footprint "eagle-import:DO-214AA")
      (libsource (lib "eagle-import") (part "P6SMBXXASMB"))
    )
    (comp (ref "D4")
      (value "5v1")
      (footprint "eagle-import:SMB")
      (fields (field (name "SPICEPREFIX") "D"))
      (libsource (lib "eagle-import") (part "Z-DIODESMB"))
    )
    (comp (ref "D7")
      (value "BZT52C12")
      (footprint "eagle-import:SOD-123")
      (libsource (lib "eagle-import") (part "Z-DIODESOD123"))
    )
    (comp (ref "IC4")
      (value "ADR01_02_03")
      (footprint "eagle-import:SOIC8")
      (libsource (lib "eagle-import") (part "ADR01_02_03"))
    )
    (comp (ref "IC5")
      (value "TLS115B0EJXUMA1")
      (footprint "eagle-import:PG-DSO-8")
      (fields (field (name "MOUSER_PART_NUMBER") "726-TLS115B0EJXUMA1"))
      (libsource (lib "eagle-import") (part "TLS115B0EJXUMA1"))
    )
    (comp (ref "IC6")
      (value "TLE42754D")
      (footprint "eagle-import:TO252-51")
      (libsource (lib "eagle-import") (part "TLE42754D"))
    )
    (comp (ref "Q2")
      (value "2N7002")
      (footprint "eagle-import:SOT-23")
      (libsource (lib "eagle-import") (part "BSS123"))
    )
    (comp (ref "Q3")
      (value "MOSFET-P")
      (footprint "eagle-import:SOT23-R")
      (libsource (lib "eagle-import") (part "MOSFET-P"))
    )
    (comp (ref "R1")
      (value "4k7")
      (footprint "eagle-import:R0805")
      (libsource (lib "eagle-import") (part "R-EU_R0805"))
    )
    (comp (ref "R24")
      (value "82k")
      (footprint "eagle-import:R0805")
      (libsource (lib "eagle-import") (part "R-EU_R0805"))
    )
    (comp (ref "R25")
      (value "33k")
      (footprint "eagle-import:R0805")
      (libsource (lib "eagle-import") (part "R-EU_R0805"))
    )
    (comp (ref "R26")
      (value "1k")
      (footprint "eagle-import:R0805")
      (libsource (lib "eagle-import") (part "R-EU_R0805"))
    )
    (comp (ref "R27")
      (value "10k")
      (footprint "eagle-import:R0805")
      (libsource (lib "eagle-import") (part "R-EU_R0805"))
    )
    (comp (ref "R30")
      (value "100k")
      (footprint "eagle-import:R0805")
      (libsource (lib "eagle-import") (part "R-EU_R0805"))
    )
    (comp (ref "R31")
      (value "22k")
      (footprint "eagle-import:R0805")
      (libsource (lib "eagle-import") (part "R-EU_R0805"))
    )
    (comp (ref "R32")
      (value "100k")
      (footprint "eagle-import:R0805")
      (libsource (lib "eagle-import") (part "R-EU_R0805"))
    )
    (comp (ref "IC8")
      (value "BM2LB150FJ-CE2")
      (footprint "eagle-import:SOIC127P600X165-8N")
      (libsource (lib "eagle-import") (part "BM2LB150FJ-CE2"))
    )
  )
  (nets
    (net (code "1") (name "5.0V") (class "Default")
      (node (ref "C1") (pin "1") (pinfunction "1_1") (pintype "passive"))
      (node (ref "C19") (pin "1") (pinfunction "1_1") (pintype "passive"))
      (node (ref "C2") (pin "1") (pinfunction "1_1") (pintype "passive"))
      (node (ref "C3") (pin "1") (pinfunction "1_1") (pintype "passive"))
      (node (ref "C32") (pin "1") (pinfunction "1_1") (pintype "passive"))
      (node (ref "C36") (pin "1") (pinfunction "1_1") (pintype "passive"))
      (node (ref "C39") (pin "1") (pinfunction "1_1") (pintype "passive"))
      (node (ref "C4") (pin "1") (pinfunction "1_1") (pintype "passive"))
      (node (ref "C5") (pin "1") (pinfunction "1_1") (pintype "passive"))
      (node (ref "C8") (pin "1") (pinfunction "1_1") (pintype "passive"))
      (node (ref "IC1") (pin "21") (pinfunction "VCC_21") (pintype "power_in"))
      (node (ref "IC1") (pin "52") (pinfunction "VCC_52") (pintype "power_in"))
      (node (ref "IC1") (pin "64") (pinfunction "AVCC_64") (pintype "bidirectional"))
      (node (ref "IC10") (pin "8") (pinfunction "VDD_8") (pintype "bidirectional"))
      (node (ref "IC11") (pin "1") (pinfunction "VDD_1") (pintype "bidirectional"))
      (node (ref "IC12") (pin "1") (pinfunction "ADDR_1") (pintype "bidirectional"))
      (node (ref "IC12") (pin "8") (pinfunction "VDD_8") (pintype "bidirectional"))
      (node (ref "IC3") (pin "3") (pinfunction "VCC_3") (pintype "power_in"))
      (node (ref "IC6") (pin "4") (pinfunction "Q_4") (pintype "bidirectional"))
      (node (ref "IC7") (pin "19") (pinfunction "VCC_19") (pintype "bidirectional"))
      (node (ref "IC9") (pin "19") (pinfunction "VCC_19") (pintype "bidirectional"))
      (node (ref "R1") (pin "2") (pinfunction "2_2") (pintype "passive"))
      (node (ref "R22") (pin "2") (pinfunction "2_2") (pintype "passive"))
      (node (ref "R23") (pin "2") (pinfunction "2_2") (pintype "passive"))
      (node (ref "R27") (pin "2") (pinfunction "2_2") (pintype "passive"))
    )
    (net (code "2") (name "AGND") (class "Default")
      (node (ref "C13") (pin "2") (pinfunction "2_2") (pintype "passive"))
      (node (ref "C14") (pin "2") (pinfunction "2_2") (pintype "passive"))
      (node (ref "C16") (pin "2") (pinfunction "2_2") (pintype "passive"))
      (node (ref "C17") (pin "2") (pinfunction "2_2") (pintype "passive"))
      (node (ref "C18") (pin "2") (pinfunction "2_2") (pintype "passive"))
      (node (ref "C20") (pin "2") (pinfunction "2_2") (pintype "passive"))
      (node (ref "C21") (pin "2") (pinfunction "2_2") (pintype "passive"))
      (node (ref "C23") (pin "2") (pinfunction "2_2") (pintype "passive"))
      (node (ref "C24") (pin "2") (pinfunction "2_2") (pintype "passive"))
      (node (ref "C26") (pin "2") (pinfunction "2_2") (pintype "passive"))
      (node (ref "C27") (pin "2") (pinfunction "2_2") (pintype "passive"))
      (node (ref "C28") (pin "2") (pinfunction "2_2") (pintype "passive"))
      (node (ref "C29") (pin "2") (pinfunction "2_2") (pintype "passive"))
      (node (ref "C30") (pin "2") (pinfunction "2_2") (pintype "passive"))
      (node (ref "C33") (pin "2") (pinfunction "2_2") (pintype "passive"))
      (node (ref "C34") (pin "2") (pinfunction "2_2") (pintype "passive"))
      (node (ref "C39") (pin "2") (pinfunction "2_2") (pintype "passive"))
      (node (ref "C40") (pin "2") (pinfunction "2_2") (pintype "passive"))
      (node (ref "C41") (pin "2") (pinfunction "2_2") (pintype "passive"))
      (node (ref "C42") (pin "2") (pinfunction "2_2") (pintype "passive"))
      (node (ref "C5") (pin "2") (pinfunction "2_2") (pintype "passive"))
      (node (ref "C6") (pin "2") (pinfunction "2_2") (pintype "passive"))
      (node (ref "IC1") (pin "63") (pinfunction "AGND_63") (pintype "bidirectional"))
      (node (ref "IC11") (pin "5") (pinfunction "GND_5") (pintype "bidirectional"))
      (node (ref "IC11") (pin "8") (pinfunction "A0_8") (pintype "bidirectional"))
      (node (ref "IC4") (pin "4") (pinfunction "GND_4") (pintype "bidirectional"))
      (node (ref "IC5") (pin "3") (pinfunction "GND_3") (pintype "bidirectional"))
      (node (ref "IC5") (pin "9") (pinfunction "GND_9") (pintype "bidirectional"))
      (node (ref "IC7") (pin "28") (pinfunction "GNDS_28") (pintype "bidirectional"))
      (node (ref "IC9") (pin "28") (pinfunction "GNDS_28") (pintype "bidirectional"))
    )
    (net (code "3") (name "ANALOG1") (class "Default")
      (node (ref "C41") (pin "1") (pinfunction "1_1") (pintype "passive"))
      (node (ref "J1") (pin "A11") (pinfunction "A11_A11") (pintype "bidirectional"))
      (node (ref "R28") (pin "2") (pinfunction "2_2") (pintype "passive"))
    )
    (net (code "4") (name "ANALOG2") (class "Default")
      (node (ref "C42") (pin "1") (pinfunction "1_1") (pintype "passive"))
      (node (ref "J1") (pin "A2") (pinfunction "A2_A2") (pintype "bidirectional"))
      (node (ref "R29") (pin "2") (pinfunction "2_2") (pintype "passive"))
    )
    (net (code "5") (name "AREF") (class "Default")
      (node (ref "C20") (pin "1") (pinfunction "1_1") (pintype "passive"))
      (node (ref "C33") (pin "1") (pinfunction "1_1") (pintype "passive"))
      (node (ref "C40") (pin "1") (pinfunction "1_1") (pintype "passive"))
      (node (ref "IC11") (pin "4") (pinfunction "REFIN_4") (pintype "bidirectional"))
      (node (ref "IC5") (pin "1") (pinfunction "OUT_1") (pintype "bidirectional"))
      (node (ref "IC7") (pin "5") (pinfunction "VCCS_5") (pintype "bidirectional"))
      (node (ref "IC9") (pin "5") (pinfunction "VCCS_5") (pintype "bidirectional"))
    )
    (net (code "6") (name "CAN_H") (class "Default")
      (node (ref "D1") (pin "1") (pinfunction "1_1") (pintype "passive"))
      (node (ref "IC3") (pin "7") (pinfunction "CANH_7") (pintype "bidirectional"))
      (node (ref "J1") (pin "A9") (pinfunction "A9_A9") (pintype "bidirectional"))
    )
    (net (code "7") (name "CAN_L") (class "Default")
      (node (ref "D1") (pin "2") (pinfunction "2_2") (pintype "passive"))
      (node (ref "IC3") (pin "6") (pinfunction "CANL_6") (pintype "bidirectional"))
      (node (ref "J1") (pin "A4") (pinfunction "A4_A4") (pintype "bidirectional"))
    )
    (net (code "8") (name "D+") (class "Default")
      (node (ref "J1") (pin "A8") (pinfunction "A8_A8") (pintype "bidirectional"))
      (node (ref "R31") (pin "1") (pinfunction "1_1") (pintype "passive"))
    )
    (net (code "9") (name "DIAHD1") (class "Default")
      (node (ref "IC8") (pin "7") (pinfunction "OUT1_7") (pintype "bidirectional"))
      (node (ref "IC8") (pin "8") (pinfunction "OUT1_8") (pintype "bidirectional"))
      (node (ref "R9") (pin "2") (pinfunction "2_2") (pintype "passive"))
    )
    (net (code "10") (name "DIAHD2") (class "Default")
      (node (ref "IC8") (pin "5") (pinfunction "OUT2_5") (pintype "bidirectional"))
      (node (ref "IC8") (pin "6") (pinfunction "OUT2_6") (pintype "bidirectional"))
      (node (ref "R20") (pin "2") (pinfunction "2_2") (pintype "passive"))
    )
    (net (code "11") (name "DIAHG1") (class "Default")
      (node (ref "IC1") (pin "15") (pinfunction "(OC1A)PB5_15") (pintype "bidirectional"))
      (node (ref "IC7") (pin "4") (pinfunction "DIAHG_4") (pintype "bidirectional"))
      (node (ref "IC8") (pin "2") (pinfunction "IN1_2") (pintype "bidirectional"))
    )
    (net (code "12") (name "DIAHG2") (class "Default")
      (node (ref "IC1") (pin "16") (pinfunction "(OC1B)PB6_16") (pintype "bidirectional"))
      (node (ref "IC8") (pin "4") (pinfunction "IN2_4") (pintype "bidirectional"))
      (node (ref "IC9") (pin "4") (pinfunction "DIAHG_4") (pintype "bidirectional"))
    )
    (net (code "13") (name "GND") (class "Default")
      (node (ref "C1") (pin "2") (pinfunction "2_2") (pintype "passive"))
      (node (ref "C10") (pin "2") (pinfunction "2_2") (pintype "passive"))
      (node (ref "C11") (pin "2") (pinfunction "2_2") (pintype "passive"))
      (node (ref "C12") (pin "2") (pinfunction "2_2") (pintype "passive"))
      (node (ref "C19") (pin "2") (pinfunction "2_2") (pintype "passive"))
      (node (ref "C2") (pin "2") (pinfunction "2_2") (pintype "passive"))
      (node (ref "C22") (pin "1") (pinfunction "1_1") (pintype "passive"))
      (node (ref "C3") (pin "2") (pinfunction "2_2") (pintype "passive"))
      (node (ref "C31") (pin "1") (pinfunction "1_1") (pintype "passive"))
      (node (ref "C32") (pin "2") (pinfunction "2_2") (pintype "passive"))
      (node (ref "C35") (pin "2") (pinfunction "2_2") (pintype "passive"))
      (node (ref "C36") (pin "2") (pinfunction "2_2") (pintype "passive"))
      (node (ref "C4") (pin "2") (pinfunction "2_2") (pintype "passive"))
      (node (ref "C7") (pin "2") (pinfunction "2_2") (pintype "passive"))
      (node (ref "C8") (pin "2") (pinfunction "2_2") (pintype "passive"))
      (node (ref "C9") (pin "-") (pinfunction "-_-") (pintype "passive"))
      (node (ref "D1") (pin "3") (pinfunction "3_3") (pintype "passive"))
      (node (ref "D3") (pin "P$2") (pinfunction "A_P$2") (pintype "passive"))
      (node (ref "D4") (pin "A") (pinfunction "A_A") (pintype "passive"))
      (node (ref "D7") (pin "A") (pinfunction "A_A") (pintype "passive"))
      (node (ref "IC1") (pin "22") (pinfunction "GND_22") (pintype "power_in"))
      (node (ref "IC1") (pin "53") (pinfunction "GND_53") (pintype "power_in"))
      (node (ref "IC10") (pin "1") (pinfunction "ADDR_1") (pintype "bidirectional"))
      (node (ref "IC10") (pin "3") (pinfunction "GND_3") (pintype "bidirectional"))
      (node (ref "IC12") (pin "3") (pinfunction "GND_3") (pintype "bidirectional"))
      (node (ref "IC2") (pin "10") (pinfunction "GND_10") (pintype "bidirectional"))
      (node (ref "IC2") (pin "2") (pinfunction "GND_2") (pintype "bidirectional"))
      (node (ref "IC3") (pin "2") (pinfunction "GND_2") (pintype "power_in"))
      (node (ref "IC3") (pin "8") (pinfunction "S_8") (pintype "bidirectional"))
      (node (ref "IC6") (pin "5") (pinfunction "GND_5") (pintype "bidirectional"))
      (node (ref "IC7") (pin "29") (pinfunction "GND_29") (pintype "bidirectional"))
      (node (ref "IC8") (pin "1") (pinfunction "GND1_1") (pintype "bidirectional"))
      (node (ref "IC8") (pin "3") (pinfunction "GND2_3") (pintype "bidirectional"))
      (node (ref "IC9") (pin "29") (pinfunction "GND_29") (pintype "bidirectional"))
      (node (ref "J1") (pin "A1") (pinfunction "A1_A1") (pintype "bidirectional"))
      (node (ref "J1") (pin "A10") (pinfunction "A10_A10") (pintype "bidirectional"))
      (node (ref "J1") (pin "A12") (pinfunction "A12_A12") (pintype "bidirectional"))
      (node (ref "J1") (pin "A3") (pinfunction "A3_A3") (pintype "bidirectional"))
      (node (ref "J1") (pin "A5") (pinfunction "A5_A5") (pintype "bidirectional"))
      (node (ref "J1") (pin "A6") (pinfunction "A6_A6") (pintype "bidirectional"))
      (node (ref "JP1") (pin "2") (pinfunction "2_2") (pintype "passive"))
      (node (ref "Q2") (pin "2") (pinfunction "S_2") (pintype "passive"))
      (node (ref "R21") (pin "2") (pinfunction "2_2") (pintype "passive"))
      (node (ref "R25") (pin "1") (pinfunction "1_1") (pintype "passive"))
      (node (ref "R30") (pin "1") (pinfunction "1_1") (pintype "passive"))
      (node (ref "R32") (pin "2") (pinfunction "2_2") (pintype "passive"))
      (node (ref "R7") (pin "2") (pinfunction "2_2") (pintype "passive"))
    )
    (net (code "14") (name "IA1") (class "Default")
      (node (ref "IC7") (pin "2") (pinfunction "IA_2") (pintype "bidirectional"))
      (node (ref "R5") (pin "1") (pinfunction "1_1") (pintype "passive"))
      (node (ref "R6") (pin "1") (pinfunction "1_1") (pintype "passive"))
    )
    (net (code "15") (name "IA2") (class "Default")
      (node (ref "IC9") (pin "2") (pinfunction "IA_2") (pintype "bidirectional"))
      (node (ref "R17") (pin "1") (pinfunction "1_1") (pintype "passive"))
      (node (ref "R18") (pin "1") (pinfunction "1_1") (pintype "passive"))
    )
    (net (code "16") (name "IP1") (class "Default")
      (node (ref "IC7") (pin "32") (pinfunction "IP_32") (pintype "bidirectional"))
      (node (ref "R5") (pin "2") (pinfunction "2_2") (pintype "passive"))
    )
    (net (code "17") (name "IP2") (class "Default")
      (node (ref "IC9") (pin "32") (pinfunction "IP_32") (pintype "bidirectional"))
      (node (ref "R18") (pin "2") (pinfunction "2_2") (pintype "passive"))
    )
    (net (code "18") (name "MISO") (class "Default")
      (node (ref "IC1") (pin "13") (pinfunction "(MISO)PB3_13") (pintype "bidirectional"))
      (node (ref "IC7") (pin "14") (pinfunction "SO_14") (pintype "bidirectional"))
      (node (ref "IC9") (pin "14") (pinfunction "SO_14") (pintype "bidirectional"))
    )
    (net (code "19") (name "MOSI") (class "Default")
      (node (ref "IC1") (pin "12") (pinfunction "(MOSI)PB2_12") (pintype "bidirectional"))
      (node (ref "IC7") (pin "15") (pinfunction "SI_15") (pintype "bidirectional"))
      (node (ref "IC9") (pin "15") (pinfunction "SI_15") (pintype "bidirectional"))
    )
    (net (code "20") (name "Net-(C15-Pad1)") (class "Default")
      (node (ref "C15") (pin "1") (pinfunction "1_1") (pintype "passive"))
      (node (ref "R2") (pin "1") (pinfunction "1_1") (pintype "passive"))
    )
    (net (code "21") (name "Net-(C25-Pad1)") (class "Default")
      (node (ref "C25") (pin "1") (pinfunction "1_1") (pintype "passive"))
      (node (ref "R11") (pin "1") (pinfunction "1_1") (pintype "passive"))
    )
    (net (code "22") (name "Net-(C37-Pad2)") (class "Default")
      (node (ref "C37") (pin "2") (pinfunction "2_2") (pintype "passive"))
      (node (ref "C38") (pin "2") (pinfunction "2_2") (pintype "passive"))
    )
    (net (code "23") (name "Net-(D4-PadC)") (class "Default")
      (node (ref "D4") (pin "C") (pinfunction "C_C") (pintype "passive"))
      (node (ref "R24") (pin "1") (pinfunction "1_1") (pintype "passive"))
      (node (ref "R25") (pin "2") (pinfunction "2_2") (pintype "passive"))
      (node (ref "R26") (pin "1") (pinfunction "1_1") (pintype "passive"))
    )
    (net (code "24") (name "Net-(IC1-AREF)") (class "Default")
      (node (ref "C6") (pin "1") (pinfunction "1_1") (pintype "passive"))
      (node (ref "IC1") (pin "62") (pinfunction "AREF_62") (pintype "bidirectional"))
    )
    (net (code "25") (name "Net-(IC4-VOUT)") (class "Default")
      (node (ref "C13") (pin "1") (pinfunction "1_1") (pintype "passive"))
      (node (ref "IC4") (pin "6") (pinfunction "VOUT_6") (pintype "bidirectional"))
      (node (ref "IC5") (pin "5") (pinfunction "ADJ_5") (pintype "bidirectional"))
    )
    (net (code "26") (name "Net-(IC6-D)") (class "Default")
      (node (ref "C7") (pin "1") (pinfunction "1_1") (pintype "passive"))
      (node (ref "IC6") (pin "3") (pinfunction "D_3") (pintype "bidirectional"))
    )
    (net (code "27") (name "Net-(IC7-CF)") (class "Default")
      (node (ref "C18") (pin "1") (pinfunction "1_1") (pintype "passive"))
      (node (ref "IC7") (pin "26") (pinfunction "CF_26") (pintype "bidirectional"))
      (node (ref "R8") (pin "1") (pinfunction "1_1") (pintype "passive"))
    )
    (net (code "28") (name "Net-(IC7-CM)") (class "Default")
      (node (ref "C15") (pin "2") (pinfunction "2_2") (pintype "passive"))
      (node (ref "IC7") (pin "11") (pinfunction "CM_11") (pintype "bidirectional"))
    )
    (net (code "29") (name "Net-(IC7-DIAHD)") (class "Default")
      (node (ref "IC7") (pin "6") (pinfunction "DIAHD_6") (pintype "bidirectional"))
      (node (ref "R9") (pin "1") (pinfunction "1_1") (pintype "passive"))
    )
    (net (code "30") (name "Net-(IC7-OSZ)") (class "Default")
      (node (ref "IC7") (pin "3") (pinfunction "OSZ_3") (pintype "bidirectional"))
      (node (ref "R7") (pin "1") (pinfunction "1_1") (pintype "passive"))
    )
    (net (code "31") (name "Net-(IC7-RF)") (class "Default")
      (node (ref "IC7") (pin "27") (pinfunction "RF_27") (pintype "bidirectional"))
      (node (ref "R8") (pin "2") (pinfunction "2_2") (pintype "passive"))
    )
    (net (code "32") (name "Net-(IC7-RM)") (class "Default")
      (node (ref "IC7") (pin "10") (pinfunction "RM_10") (pintype "bidirectional"))
      (node (ref "R2") (pin "2") (pinfunction "2_2") (pintype "passive"))
    )
    (net (code "33") (name "Net-(IC7-RS)") (class "Default")
      (node (ref "IC7") (pin "8") (pinfunction "RS_8") (pintype "bidirectional"))
      (node (ref "R12") (pin "2") (pinfunction "2_2") (pintype "passive"))
    )
    (net (code "34") (name "Net-(IC7-UN)") (class "Default")
      (node (ref "C23") (pin "1") (pinfunction "1_1") (pintype "passive"))
      (node (ref "IC7") (pin "31") (pinfunction "UN_31") (pintype "bidirectional"))
      (node (ref "R10") (pin "2") (pinfunction "2_2") (pintype "passive"))
    )
    (net (code "35") (name "Net-(IC7-UP)") (class "Default")
      (node (ref "IC7") (pin "22") (pinfunction "UP_22") (pintype "bidirectional"))
      (node (ref "R3") (pin "1") (pinfunction "1_1") (pintype "passive"))
      (node (ref "R4") (pin "1") (pinfunction "1_1") (pintype "passive"))
      (node (ref "R6") (pin "2") (pinfunction "2_2") (pintype "passive"))
    )
    (net (code "36") (name "Net-(IC7-US)") (class "Default")
      (node (ref "IC7") (pin "21") (pinfunction "US_21") (pintype "bidirectional"))
      (node (ref "R4") (pin "2") (pinfunction "2_2") (pintype "passive"))
    )
    (net (code "37") (name "Net-(IC7-VCCSS)") (class "Default")
      (node (ref "C21") (pin "1") (pinfunction "1_1") (pintype "passive"))
      (node (ref "IC7") (pin "18") (pinfunction "VCCSS_18") (pintype "bidirectional"))
    )
    (net (code "38") (name "Net-(IC9-CF)") (class "Default")
      (node (ref "C28") (pin "1") (pinfunction "1_1") (pintype "passive"))
      (node (ref "IC9") (pin "26") (pinfunction "CF_26") (pintype "bidirectional"))
      (node (ref "R19") (pin "1") (pinfunction "1_1") (pintype "passive"))
    )
    (net (code "39") (name "Net-(IC9-CM)") (class "Default")
      (node (ref "C25") (pin "2") (pinfunction "2_2") (pintype "passive"))
      (node (ref "IC9") (pin "11") (pinfunction "CM_11") (pintype "bidirectional"))
    )
    (net (code "40") (name "Net-(IC9-DIAHD)") (class "Default")
      (node (ref "IC9") (pin "6") (pinfunction "DIAHD_6") (pintype "bidirectional"))
      (node (ref "R20") (pin "1") (pinfunction "1_1") (pintype "passive"))
    )
    (net (code "41") (name "Net-(IC9-OSZ)") (class "Default")
      (node (ref "IC9") (pin "3") (pinfunction "OSZ_3") (pintype "bidirectional"))
      (node (ref "R21") (pin "1") (pinfunction "1_1") (pintype "passive"))
    )
    (net (code "42") (name "Net-(IC9-RF)") (class "Default")
      (node (ref "IC9") (pin "27") (pinfunction "RF_27") (pintype "bidirectional"))
      (node (ref "R19") (pin "2") (pinfunction "2_2") (pintype "passive"))
    )
    (net (code "43") (name "Net-(IC9-RM)") (class "Default")
      (node (ref "IC9") (pin "10") (pinfunction "RM_10") (pintype "bidirectional"))
      (node (ref "R11") (pin "2") (pinfunction "2_2") (pintype "passive"))
    )
    (net (code "44") (name "Net-(IC9-RS)") (class "Default")
      (node (ref "IC9") (pin "8") (pinfunction "RS_8") (pintype "bidirectional"))
      (node (ref "R15") (pin "2") (pinfunction "2_2") (pintype "passive"))
    )
    (net (code "45") (name "Net-(IC9-UN)") (class "Default")
      (node (ref "C26") (pin "1") (pinfunction "1_1") (pintype "passive"))
      (node (ref "IC9") (pin "31") (pinfunction "UN_31") (pintype "bidirectional"))
      (node (ref "R13") (pin "2") (pinfunction "2_2") (pintype "passive"))
    )
    (net (code "46") (name "Net-(IC9-UP)") (class "Default")
      (node (ref "IC9") (pin "22") (pinfunction "UP_22") (pintype "bidirectional"))
      (node (ref "R14") (pin "1") (pinfunction "1_1") (pintype "passive"))
      (node (ref "R16") (pin "1") (pinfunction "1_1") (pintype "passive"))
      (node (ref "R17") (pin "2") (pinfunction "2_2") (pintype "passive"))
    )
    (net (code "47") (name "Net-(IC9-US)") (class "Default")
      (node (ref "IC9") (pin "21") (pinfunction "US_21") (pintype "bidirectional"))
      (node (ref "R16") (pin "2") (pinfunction "2_2") (pintype "passive"))
    )
    (net (code "48") (name "Net-(IC9-VCCSS)") (class "Default")
      (node (ref "C34") (pin "1") (pinfunction "1_1") (pintype "passive"))
      (node (ref "IC9") (pin "18") (pinfunction "VCCSS_18") (pintype "bidirectional"))
    )
    (net (code "49") (name "Net-(IC11-VOUTA)") (class "Default")
      (node (ref "IC11") (pin "2") (pinfunction "VOUTA_2") (pintype "bidirectional"))
      (node (ref "R28") (pin "1") (pinfunction "1_1") (pintype "passive"))
    )
    (net (code "50") (name "Net-(IC11-VOUTB)") (class "Default")
      (node (ref "IC11") (pin "3") (pinfunction "VOUTB_3") (pintype "bidirectional"))
      (node (ref "R29") (pin "1") (pinfunction "1_1") (pintype "passive"))
    )
    (net (code "51") (name "Net-(Q2-G)") (class "Default")
      (node (ref "D7") (pin "C") (pinfunction "C_C") (pintype "passive"))
      (node (ref "Q2") (pin "1") (pinfunction "G_1") (pintype "passive"))
      (node (ref "R30") (pin "2") (pinfunction "2_2") (pintype "passive"))
      (node (ref "R31") (pin "2") (pinfunction "2_2") (pintype "passive"))
    )
    (net (code "52") (name "Net-(Q3-G)") (class "Default")
      (node (ref "D2") (pin "A") (pinfunction "A_A") (pintype "passive"))
      (node (ref "Q3") (pin "1") (pinfunction "G_1") (pintype "passive"))
      (node (ref "R32") (pin "1") (pinfunction "1_1") (pintype "passive"))
    )
    (net (code "53") (name "RXCAN") (class "Default")
      (node (ref "IC1") (pin "31") (pinfunction "(RXCAN/T1)PD6_31") (pintype "bidirectional"))
      (node (ref "IC3") (pin "4") (pinfunction "RXD_4") (pintype "bidirectional"))
    )
    (net (code "54") (name "RXD0") (class "Default")
      (node (ref "IC1") (pin "2") (pinfunction "(RXD0/PDI)PE0_2") (pintype "bidirectional"))
      (node (ref "JP1") (pin "3") (pinfunction "3_3") (pintype "passive"))
    )
    (net (code "55") (name "SCK") (class "Default")
      (node (ref "IC1") (pin "11") (pinfunction "(SCK)PB1_11") (pintype "bidirectional"))
      (node (ref "IC7") (pin "13") (pinfunction "SCK_13") (pintype "bidirectional"))
      (node (ref "IC9") (pin "13") (pinfunction "SCK_13") (pintype "bidirectional"))
    )
    (net (code "56") (name "SCL") (class "Default")
      (node (ref "IC1") (pin "25") (pinfunction "(SCL/INT0)PD0_25") (pintype "bidirectional"))
      (node (ref "IC10") (pin "10") (pinfunction "SCL_10") (pintype "bidirectional"))
      (node (ref "IC11") (pin "7") (pinfunction "SCL_7") (pintype "bidirectional"))
      (node (ref "IC12") (pin "10") (pinfunction "SCL_10") (pintype "bidirectional"))
      (node (ref "R23") (pin "1") (pinfunction "1_1") (pintype "passive"))
    )
    (net (code "57") (name "SDA") (class "Default")
      (node (ref "IC1") (pin "26") (pinfunction "(SDA/INT1)PD1_26") (pintype "bidirectional"))
      (node (ref "IC10") (pin "9") (pinfunction "SDA_9") (pintype "bidirectional"))
      (node (ref "IC11") (pin "6") (pinfunction "SDA_6") (pintype "bidirectional"))
      (node (ref "IC12") (pin "9") (pinfunction "SDA_9") (pintype "bidirectional"))
      (node (ref "R22") (pin "1") (pinfunction "1_1") (pintype "passive"))
    )
    (net (code "58") (name "TCK") (class "Default")
      (node (ref "IC1") (pin "57") (pinfunction "PF4(ADC4/TCK)_57") (pintype "input"))
      (node (ref "IC2") (pin "1") (pinfunction "TCK_1") (pintype "bidirectional"))
    )
    (net (code "59") (name "TDI") (class "Default")
      (node (ref "IC1") (pin "54") (pinfunction "PF7(ADC7/TDI)_54") (pintype "input"))
      (node (ref "IC2") (pin "9") (pinfunction "TDI_9") (pintype "bidirectional"))
    )
    (net (code "60") (name "TDO") (class "Default")
      (node (ref "IC1") (pin "55") (pinfunction "PF6(ADC6/TDO)_55") (pintype "input"))
      (node (ref "IC2") (pin "3") (pinfunction "TDO_3") (pintype "bidirectional"))
    )
    (net (code "61") (name "TMS") (class "Default")
      (node (ref "IC1") (pin "56") (pinfunction "PF5(ADC5/TMS)_56") (pintype "input"))
      (node (ref "IC2") (pin "5") (pinfunction "TMS_5") (pintype "bidirectional"))
    )
    (net (code "62") (name "TXCAN") (class "Default")
      (node (ref "IC1") (pin "30") (pinfunction "(TXCAN/XCK1)PD5_30") (pintype "bidirectional"))
      (node (ref "IC3") (pin "1") (pinfunction "TXD_1") (pintype "bidirectional"))
    )
    (net (code "63") (name "TXD0") (class "Default")
      (node (ref "IC1") (pin "3") (pinfunction "(TXD0/PDO)PE1_3") (pintype "bidirectional"))
      (node (ref "JP1") (pin "1") (pinfunction "1_1") (pintype "passive"))
    )
    (net (code "64") (name "UA1") (class "Default")
      (node (ref "C17") (pin "1") (pinfunction "1_1") (pintype "passive"))
      (node (ref "IC10") (pin "4") (pinfunction "AIN0_4") (pintype "bidirectional"))
      (node (ref "IC7") (pin "23") (pinfunction "UA_23") (pintype "bidirectional"))
    )
    (net (code "65") (name "UA2") (class "Default")
      (node (ref "C29") (pin "1") (pinfunction "1_1") (pintype "passive"))
      (node (ref "IC12") (pin "4") (pinfunction "AIN0_4") (pintype "bidirectional"))
      (node (ref "IC9") (pin "23") (pinfunction "UA_23") (pintype "bidirectional"))
    )
    (net (code "66") (name "UN1") (class "Default")
      (node (ref "C24") (pin "1") (pinfunction "1_1") (pintype "passive"))
      (node (ref "R10") (pin "1") (pinfunction "1_1") (pintype "passive"))
      (node (ref "R3") (pin "2") (pinfunction "2_2") (pintype "passive"))
    )
    (net (code "67") (name "UN2") (class "Default")
      (node (ref "C27") (pin "1") (pinfunction "1_1") (pintype "passive"))
      (node (ref "R13") (pin "1") (pinfunction "1_1") (pintype "passive"))
      (node (ref "R14") (pin "2") (pinfunction "2_2") (pintype "passive"))
    )
    (net (code "68") (name "UR1") (class "Default")
      (node (ref "C16") (pin "1") (pinfunction "1_1") (pintype "passive"))
      (node (ref "IC10") (pin "5") (pinfunction "AIN1_5") (pintype "bidirectional"))
      (node (ref "IC7") (pin "12") (pinfunction "UR_12") (pintype "bidirectional"))
    )
    (net (code "69") (name "UR2") (class "Default")
      (node (ref "C30") (pin "1") (pinfunction "1_1") (pintype "passive"))
      (node (ref "IC12") (pin "5") (pinfunction "AIN1_5") (pintype "bidirectional"))
      (node (ref "IC9") (pin "12") (pinfunction "UR_12") (pintype "bidirectional"))
    )
    (net (code "70") (name "VBAT") (class "Default")
      (node (ref "J1") (pin "A7") (pinfunction "A7_A7") (pintype "bidirectional"))
      (node (ref "Q3") (pin "3") (pinfunction "D_3") (pintype "passive"))
    )
    (net (code "71") (name "VBAT_PROT") (class "Default")
      (node (ref "C10") (pin "1") (pinfunction "1_1") (pintype "passive"))
      (node (ref "C11") (pin "1") (pinfunction "1_1") (pintype "passive"))
      (node (ref "C12") (pin "1") (pinfunction "1_1") (pintype "passive"))
      (node (ref "C14") (pin "1") (pinfunction "1_1") (pintype "passive"))
      (node (ref "C22") (pin "2") (pinfunction "2_2") (pintype "passive"))
      (node (ref "C31") (pin "2") (pinfunction "2_2") (pintype "passive"))
      (node (ref "C9") (pin "+") (pinfunction "+_+") (pintype "passive"))
      (node (ref "D2") (pin "C") (pinfunction "C_C") (pintype "passive"))
      (node (ref "D3") (pin "P$1") (pinfunction "C_P$1") (pintype "passive"))
      (node (ref "IC4") (pin "2") (pinfunction "VIN_2") (pintype "bidirectional"))
      (node (ref "IC5") (pin "7") (pinfunction "EN_7") (pintype "bidirectional"))
      (node (ref "IC5") (pin "8") (pinfunction "IN_8") (pintype "bidirectional"))
      (node (ref "IC6") (pin "1") (pinfunction "I_1") (pintype "bidirectional"))
      (node (ref "IC7") (pin "30") (pinfunction "UB_30") (pintype "bidirectional"))
      (node (ref "IC9") (pin "30") (pinfunction "UB_30") (pintype "bidirectional"))
      (node (ref "Q3") (pin "2") (pinfunction "S_2") (pintype "passive"))
      (node (ref "R24") (pin "2") (pinfunction "2_2") (pintype "passive"))
    )
    (net (code "72") (name "VM1") (class "Default")
      (node (ref "IC7") (pin "20") (pinfunction "VM_20") (pintype "bidirectional"))
      (node (ref "R12") (pin "1") (pinfunction "1_1") (pintype "passive"))
    )
    (net (code "73") (name "VM2") (class "Default")
      (node (ref "IC9") (pin "20") (pinfunction "VM_20") (pintype "bidirectional"))
      (node (ref "R15") (pin "1") (pinfunction "1_1") (pintype "passive"))
    )
    (net (code "74") (name "VOL_BAT") (class "Default")
      (node (ref "C35") (pin "1") (pinfunction "1_1") (pintype "passive"))
      (node (ref "IC10") (pin "6") (pinfunction "AIN2_6") (pintype "bidirectional"))
      (node (ref "R26") (pin "2") (pinfunction "2_2") (pintype "passive"))
    )
    (net (code "75") (name "XTAL1") (class "Default")
      (node (ref "C37") (pin "1") (pinfunction "1_1") (pintype "passive"))
      (node (ref "IC1") (pin "24") (pinfunction "XTAL1_24") (pintype "bidirectional"))
      (node (ref "Q1") (pin "2") (pinfunction "2_2") (pintype "passive"))
    )
    (net (code "76") (name "XTAL2") (class "Default")
      (node (ref "C38") (pin "1") (pinfunction "1_1") (pintype "passive"))
      (node (ref "IC1") (pin "23") (pinfunction "XTAL2_23") (pintype "bidirectional"))
      (node (ref "Q1") (pin "1") (pinfunction "1_1") (pintype "passive"))
    )
    (net (code "77") (name "unconnected-(IC1-(A8)PC0-Pad35)") (class "Default")
      (node (ref "IC1") (pin "35") (pinfunction "(A8)PC0_35") (pintype "output"))
    )
    (net (code "78") (name "unconnected-(IC1-(A9)PC1-Pad36)") (class "Default")
      (node (ref "IC1") (pin "36") (pinfunction "(A9)PC1_36") (pintype "output"))
    )
    (net (code "79") (name "unconnected-(IC1-(A10)PC2-Pad37)") (class "Default")
      (node (ref "IC1") (pin "37") (pinfunction "(A10)PC2_37") (pintype "output"))
    )
    (net (code "80") (name "unconnected-(IC1-(A11)PC3-Pad38)") (class "Default")
      (node (ref "IC1") (pin "38") (pinfunction "(A11)PC3_38") (pintype "output"))
    )
    (net (code "81") (name "unconnected-(IC1-(A12)PC4-Pad39)") (class "Default")
      (node (ref "IC1") (pin "39") (pinfunction "(A12)PC4_39") (pintype "output"))
    )
    (net (code "82") (name "unconnected-(IC1-(A13)PC5-Pad40)") (class "Default")
      (node (ref "IC1") (pin "40") (pinfunction "(A13)PC5_40") (pintype "output"))
    )
    (net (code "83") (name "unconnected-(IC1-(A14)PC6-Pad41)") (class "Default")
      (node (ref "IC1") (pin "41") (pinfunction "(A14)PC6_41") (pintype "output"))
    )
    (net (code "84") (name "unconnected-(IC1-(A15{slash}CLKO)PC7-Pad42)") (class "Default")
      (node (ref "IC1") (pin "42") (pinfunction "(A15/CLKO)PC7_42") (pintype "output"))
    )
    (net (code "85") (name "unconnected-(IC1-(AD0)PA0-Pad51)") (class "Default")
      (node (ref "IC1") (pin "51") (pinfunction "(AD0)PA0_51") (pintype "bidirectional"))
    )
    (net (code "86") (name "unconnected-(IC1-(AD1)PA1-Pad50)") (class "Default")
      (node (ref "IC1") (pin "50") (pinfunction "(AD1)PA1_50") (pintype "bidirectional"))
    )
    (net (code "87") (name "unconnected-(IC1-(AD2)PA2-Pad49)") (class "Default")
      (node (ref "IC1") (pin "49") (pinfunction "(AD2)PA2_49") (pintype "bidirectional"))
    )
    (net (code "88") (name "unconnected-(IC1-(AD3)PA3-Pad48)") (class "Default")
      (node (ref "IC1") (pin "48") (pinfunction "(AD3)PA3_48") (pintype "bidirectional"))
    )
    (net (code "89") (name "unconnected-(IC1-(AD4)PA4-Pad47)") (class "Default")
      (node (ref "IC1") (pin "47") (pinfunction "(AD4)PA4_47") (pintype "bidirectional"))
    )
    (net (code "90") (name "unconnected-(IC1-(AD5)PA5-Pad46)") (class "Default")
      (node (ref "IC1") (pin "46") (pinfunction "(AD5)PA5_46") (pintype "bidirectional"))
    )
    (net (code "91") (name "unconnected-(IC1-(AD6)PA6-Pad45)") (class "Default")
      (node (ref "IC1") (pin "45") (pinfunction "(AD6)PA6_45") (pintype "bidirectional"))
    )
    (net (code "92") (name "unconnected-(IC1-(AD7)PA7-Pad44)") (class "Default")
      (node (ref "IC1") (pin "44") (pinfunction "(AD7)PA7_44") (pintype "bidirectional"))
    )
    (net (code "93") (name "unconnected-(IC1-(ICP1)PD4-Pad29)") (class "Default")
      (node (ref "IC1") (pin "29") (pinfunction "(ICP1)PD4_29") (pintype "bidirectional"))
    )
    (net (code "94") (name "unconnected-(IC1-(OC0A{slash}OC1C)PB7-Pad17)") (class "Default")
      (node (ref "IC1") (pin "17") (pinfunction "(OC0A/OC1C)PB7_17") (pintype "bidirectional"))
    )
    (net (code "95") (name "unconnected-(IC1-(OC2A)PB4-Pad14)") (class "Default")
      (node (ref "IC1") (pin "14") (pinfunction "(OC2A)PB4_14") (pintype "bidirectional"))
    )
    (net (code "96") (name "unconnected-(IC1-(OC3A{slash}AIN1)PE3-Pad5)") (class "Default")
      (node (ref "IC1") (pin "5") (pinfunction "(OC3A/AIN1)PE3_5") (pintype "bidirectional"))
    )
    (net (code "97") (name "unconnected-(IC1-(OC3B{slash}INT4)PE4-Pad6)") (class "Default")
      (node (ref "IC1") (pin "6") (pinfunction "(OC3B/INT4)PE4_6") (pintype "bidirectional"))
    )
    (net (code "98") (name "unconnected-(IC1-(RXD1{slash}INT2)PD2-Pad27)") (class "Default")
      (node (ref "IC1") (pin "27") (pinfunction "(RXD1/INT2)PD2_27") (pintype "bidirectional"))
    )
    (net (code "99") (name "unconnected-(IC1-(SS)PB0-Pad10)") (class "Default")
      (node (ref "IC1") (pin "10") (pinfunction "(SS)PB0_10") (pintype "bidirectional"))
    )
    (net (code "100") (name "unconnected-(IC1-(T0)PD7-Pad32)") (class "Default")
      (node (ref "IC1") (pin "32") (pinfunction "(T0)PD7_32") (pintype "bidirectional"))
    )
    (net (code "101") (name "unconnected-(IC1-(TXD1{slash}INT3)PD3-Pad28)") (class "Default")
      (node (ref "IC1") (pin "28") (pinfunction "(TXD1/INT3)PD3_28") (pintype "bidirectional"))
    )
    (net (code "102") (name "unconnected-(IC1-PF0(ADC0)-Pad61)") (class "Default")
      (node (ref "IC1") (pin "61") (pinfunction "PF0(ADC0)_61") (pintype "input"))
    )
    (net (code "103") (name "unconnected-(IC1-PF1(ADC1)-Pad60)") (class "Default")
      (node (ref "IC1") (pin "60") (pinfunction "PF1(ADC1)_60") (pintype "input"))
    )
    (net (code "104") (name "unconnected-(IC1-PF2(ADC2)-Pad59)") (class "Default")
      (node (ref "IC1") (pin "59") (pinfunction "PF2(ADC2)_59") (pintype "input"))
    )
    (net (code "105") (name "unconnected-(IC1-PF3(ADC3)-Pad58)") (class "Default")
      (node (ref "IC1") (pin "58") (pinfunction "PF3(ADC3)_58") (pintype "input"))
    )
    (net (code "106") (name "unconnected-(IC1-PG0(~{WR})-Pad33)") (class "Default")
      (node (ref "IC1") (pin "33") (pinfunction "PG0(~{WR})_33") (pintype "input"))
    )
    (net (code "107") (name "unconnected-(IC1-PG1(~{RD})-Pad34)") (class "Default")
      (node (ref "IC1") (pin "34") (pinfunction "PG1(~{RD})_34") (pintype "input"))
    )
    (net (code "108") (name "unconnected-(IC1-PG2(ALE)-Pad43)") (class "Default")
      (node (ref "IC1") (pin "43") (pinfunction "PG2(ALE)_43") (pintype "input"))
    )
    (net (code "109") (name "unconnected-(IC1-PG3(TOSC2)-Pad18)") (class "Default")
      (node (ref "IC1") (pin "18") (pinfunction "PG3(TOSC2)_18") (pintype "input"))
    )
    (net (code "110") (name "unconnected-(IC1-PG4(TOSC1)-Pad19)") (class "Default")
      (node (ref "IC1") (pin "19") (pinfunction "PG4(TOSC1)_19") (pintype "input"))
    )
    (net (code "111") (name "unconnected-(IC2-NC-Pad7)") (class "Default")
      (node (ref "IC2") (pin "7") (pinfunction "NC_7") (pintype "no_connect"))
    )
    (net (code "112") (name "unconnected-(IC2-NTRST-Pad8)") (class "Default")
      (node (ref "IC2") (pin "8") (pinfunction "NTRST_8") (pintype "bidirectional"))
    )
    (net (code "113") (name "unconnected-(IC2-VCC-Pad4)") (class "Default")
      (node (ref "IC2") (pin "4") (pinfunction "VCC_4") (pintype "bidirectional"))
    )
    (net (code "114") (name "unconnected-(IC2-~{RESET}-Pad6)") (class "Default")
      (node (ref "IC2") (pin "6") (pinfunction "~{RESET}_6") (pintype "bidirectional"))
    )
    (net (code "115") (name "unconnected-(IC3-VREF-Pad5)") (class "Default")
      (node (ref "IC3") (pin "5") (pinfunction "VREF_5") (pintype "bidirectional"))
    )
    (net (code "116") (name "unconnected-(IC4-NIC-Pad1)") (class "Default")
      (node (ref "IC4") (pin "1") (pinfunction "NIC_1") (pintype "no_connect"))
    )
    (net (code "117") (name "unconnected-(IC4-NIC-Pad7)") (class "Default")
      (node (ref "IC4") (pin "7") (pinfunction "NIC_7") (pintype "no_connect"))
    )
    (net (code "118") (name "unconnected-(IC4-NIC-Pad8)") (class "Default")
      (node (ref "IC4") (pin "8") (pinfunction "NIC_8") (pintype "no_connect"))
    )
    (net (code "119") (name "unconnected-(IC4-TEMP-Pad3)") (class "Default")
      (node (ref "IC4") (pin "3") (pinfunction "TEMP_3") (pintype "bidirectional"))
    )
    (net (code "120") (name "unconnected-(IC4-TRIM-Pad5)") (class "Default")
      (node (ref "IC4") (pin "5") (pinfunction "TRIM_5") (pintype "bidirectional"))
    )
    (net (code "121") (name "unconnected-(IC5-NC-Pad2)") (class "Default")
      (node (ref "IC5") (pin "2") (pinfunction "NC_2") (pintype "no_connect"))
    )
    (net (code "122") (name "unconnected-(IC5-NC-Pad4)") (class "Default")
      (node (ref "IC5") (pin "4") (pinfunction "NC_4") (pintype "no_connect"))
    )
    (net (code "123") (name "unconnected-(IC5-NC-Pad6)") (class "Default")
      (node (ref "IC5") (pin "6") (pinfunction "NC_6") (pintype "no_connect"))
    )
    (net (code "124") (name "unconnected-(IC7-NC-Pad1)") (class "Default")
      (node (ref "IC7") (pin "1") (pinfunction "NC_1") (pintype "no_connect"))
    )
    (net (code "125") (name "unconnected-(IC7-NC-Pad9)") (class "Default")
      (node (ref "IC7") (pin "9") (pinfunction "NC_9") (pintype "no_connect"))
    )
    (net (code "126") (name "unconnected-(IC7-NC-Pad16)") (class "Default")
      (node (ref "IC7") (pin "16") (pinfunction "NC_16") (pintype "no_connect"))
    )
    (net (code "127") (name "unconnected-(IC7-NC-Pad24)") (class "Default")
      (node (ref "IC7") (pin "24") (pinfunction "NC_24") (pintype "no_connect"))
    )
    (net (code "128") (name "unconnected-(IC7-NC-Pad25)") (class "Default")
      (node (ref "IC7") (pin "25") (pinfunction "NC_25") (pintype "no_connect"))
    )
    (net (code "129") (name "unconnected-(IC9-NC-Pad1)") (class "Default")
      (node (ref "IC9") (pin "1") (pinfunction "NC_1") (pintype "no_connect"))
    )
    (net (code "130") (name "unconnected-(IC9-NC-Pad9)") (class "Default")
      (node (ref "IC9") (pin "9") (pinfunction "NC_9") (pintype "no_connect"))
    )
    (net (code "131") (name "unconnected-(IC9-NC-Pad16)") (class "Default")
      (node (ref "IC9") (pin "16") (pinfunction "NC_16") (pintype "no_connect"))
    )
    (net (code "132") (name "unconnected-(IC9-NC-Pad24)") (class "Default")
      (node (ref "IC9") (pin "24") (pinfunction "NC_24") (pintype "no_connect"))
    )
    (net (code "133") (name "unconnected-(IC9-NC-Pad25)") (class "Default")
      (node (ref "IC9") (pin "25") (pinfunction "NC_25") (pintype "no_connect"))
    )
    (net (code "134") (name "unconnected-(IC10-AIN3-Pad7)") (class "Default")
      (node (ref "IC10") (pin "7") (pinfunction "AIN3_7") (pintype "bidirectional"))
    )
    (net (code "135") (name "unconnected-(IC10-ALERT{slash}RDY-Pad2)") (class "Default")
      (node (ref "IC10") (pin "2") (pinfunction "ALERT/RDY_2") (pintype "bidirectional"))
    )
    (net (code "136") (name "unconnected-(IC12-AIN2-Pad6)") (class "Default")
      (node (ref "IC12") (pin "6") (pinfunction "AIN2_6") (pintype "bidirectional"))
    )
    (net (code "137") (name "unconnected-(IC12-AIN3-Pad7)") (class "Default")
      (node (ref "IC12") (pin "7") (pinfunction "AIN3_7") (pintype "bidirectional"))
    )
    (net (code "138") (name "unconnected-(IC12-ALERT{slash}RDY-Pad2)") (class "Default")
      (node (ref "IC12") (pin "2") (pinfunction "ALERT/RDY_2") (pintype "bidirectional"))
    )
    (net (code "139") (name "unconnected-(J1-PadB1)") (class "Default")
      (node (ref "J1") (pin "B1") (pinfunction "B1_B1") (pintype "bidirectional"))
    )
    (net (code "140") (name "unconnected-(J1-PadB2)") (class "Default")
      (node (ref "J1") (pin "B2") (pinfunction "B2_B2") (pintype "bidirectional"))
    )
    (net (code "141") (name "unconnected-(J1-PadB3)") (class "Default")
      (node (ref "J1") (pin "B3") (pinfunction "B3_B3") (pintype "bidirectional"))
    )
    (net (code "142") (name "unconnected-(J1-PadB4)") (class "Default")
      (node (ref "J1") (pin "B4") (pinfunction "B4_B4") (pintype "bidirectional"))
    )
    (net (code "143") (name "unconnected-(J1-PadB5)") (class "Default")
      (node (ref "J1") (pin "B5") (pinfunction "B5_B5") (pintype "bidirectional"))
    )
    (net (code "144") (name "unconnected-(J1-PadB6)") (class "Default")
      (node (ref "J1") (pin "B6") (pinfunction "B6_B6") (pintype "bidirectional"))
    )
    (net (code "145") (name "unconnected-(J1-PadB7)") (class "Default")
      (node (ref "J1") (pin "B7") (pinfunction "B7_B7") (pintype "bidirectional"))
    )
    (net (code "146") (name "unconnected-(J1-PadB8)") (class "Default")
      (node (ref "J1") (pin "B8") (pinfunction "B8_B8") (pintype "bidirectional"))
    )
    (net (code "147") (name "unconnected-(J1-PadB9)") (class "Default")
      (node (ref "J1") (pin "B9") (pinfunction "B9_B9") (pintype "bidirectional"))
    )
    (net (code "148") (name "unconnected-(J1-PadB10)") (class "Default")
      (node (ref "J1") (pin "B10") (pinfunction "B10_B10") (pintype "bidirectional"))
    )
    (net (code "149") (name "unconnected-(J1-PadB11)") (class "Default")
      (node (ref "J1") (pin "B11") (pinfunction "B11_B11") (pintype "bidirectional"))
    )
    (net (code "150") (name "unconnected-(J1-PadB12)") (class "Default")
      (node (ref "J1") (pin "B12") (pinfunction "B12_B12") (pintype "bidirectional"))
    )
    (net (code "151") (name "~{CJ_RST}") (class "Default")
      (node (ref "IC1") (pin "7") (pinfunction "(OC3C/INT5)PE5_7") (pintype "bidirectional"))
      (node (ref "IC7") (pin "7") (pinfunction "~{RST}_7") (pintype "bidirectional"))
      (node (ref "IC9") (pin "7") (pinfunction "~{RST}_7") (pintype "bidirectional"))
    )
    (net (code "152") (name "~{EXT_ACT}") (class "Default")
      (node (ref "IC1") (pin "4") (pinfunction "(XCK0/AIN0)PE2_4") (pintype "bidirectional"))
      (node (ref "Q2") (pin "3") (pinfunction "D_3") (pintype "passive"))
      (node (ref "R27") (pin "1") (pinfunction "1_1") (pintype "passive"))
    )
    (net (code "153") (name "~{RESET}") (class "Default")
      (node (ref "IC1") (pin "20") (pinfunction "~{RESET}_20") (pintype "input"))
      (node (ref "IC6") (pin "2") (pinfunction "RO_2") (pintype "bidirectional"))
      (node (ref "R1") (pin "1") (pinfunction "1_1") (pintype "passive"))
    )
    (net (code "154") (name "~{SS1}") (class "Default")
      (node (ref "IC1") (pin "9") (pinfunction "(ICP3/INT7)PE7_9") (pintype "bidirectional"))
      (node (ref "IC7") (pin "17") (pinfunction "~{SS}_17") (pintype "bidirectional"))
    )
    (net (code "155") (name "~{SS2}") (class "Default")
      (node (ref "IC1") (pin "8") (pinfunction "(T3/INT6)PE6_8") (pintype "bidirectional"))
      (node (ref "IC9") (pin "17") (pinfunction "~{SS}_17") (pintype "bidirectional"))
    )
  )
)
